# console-ifc.net
KiCad netlist of a schematic drawn in EAGLE
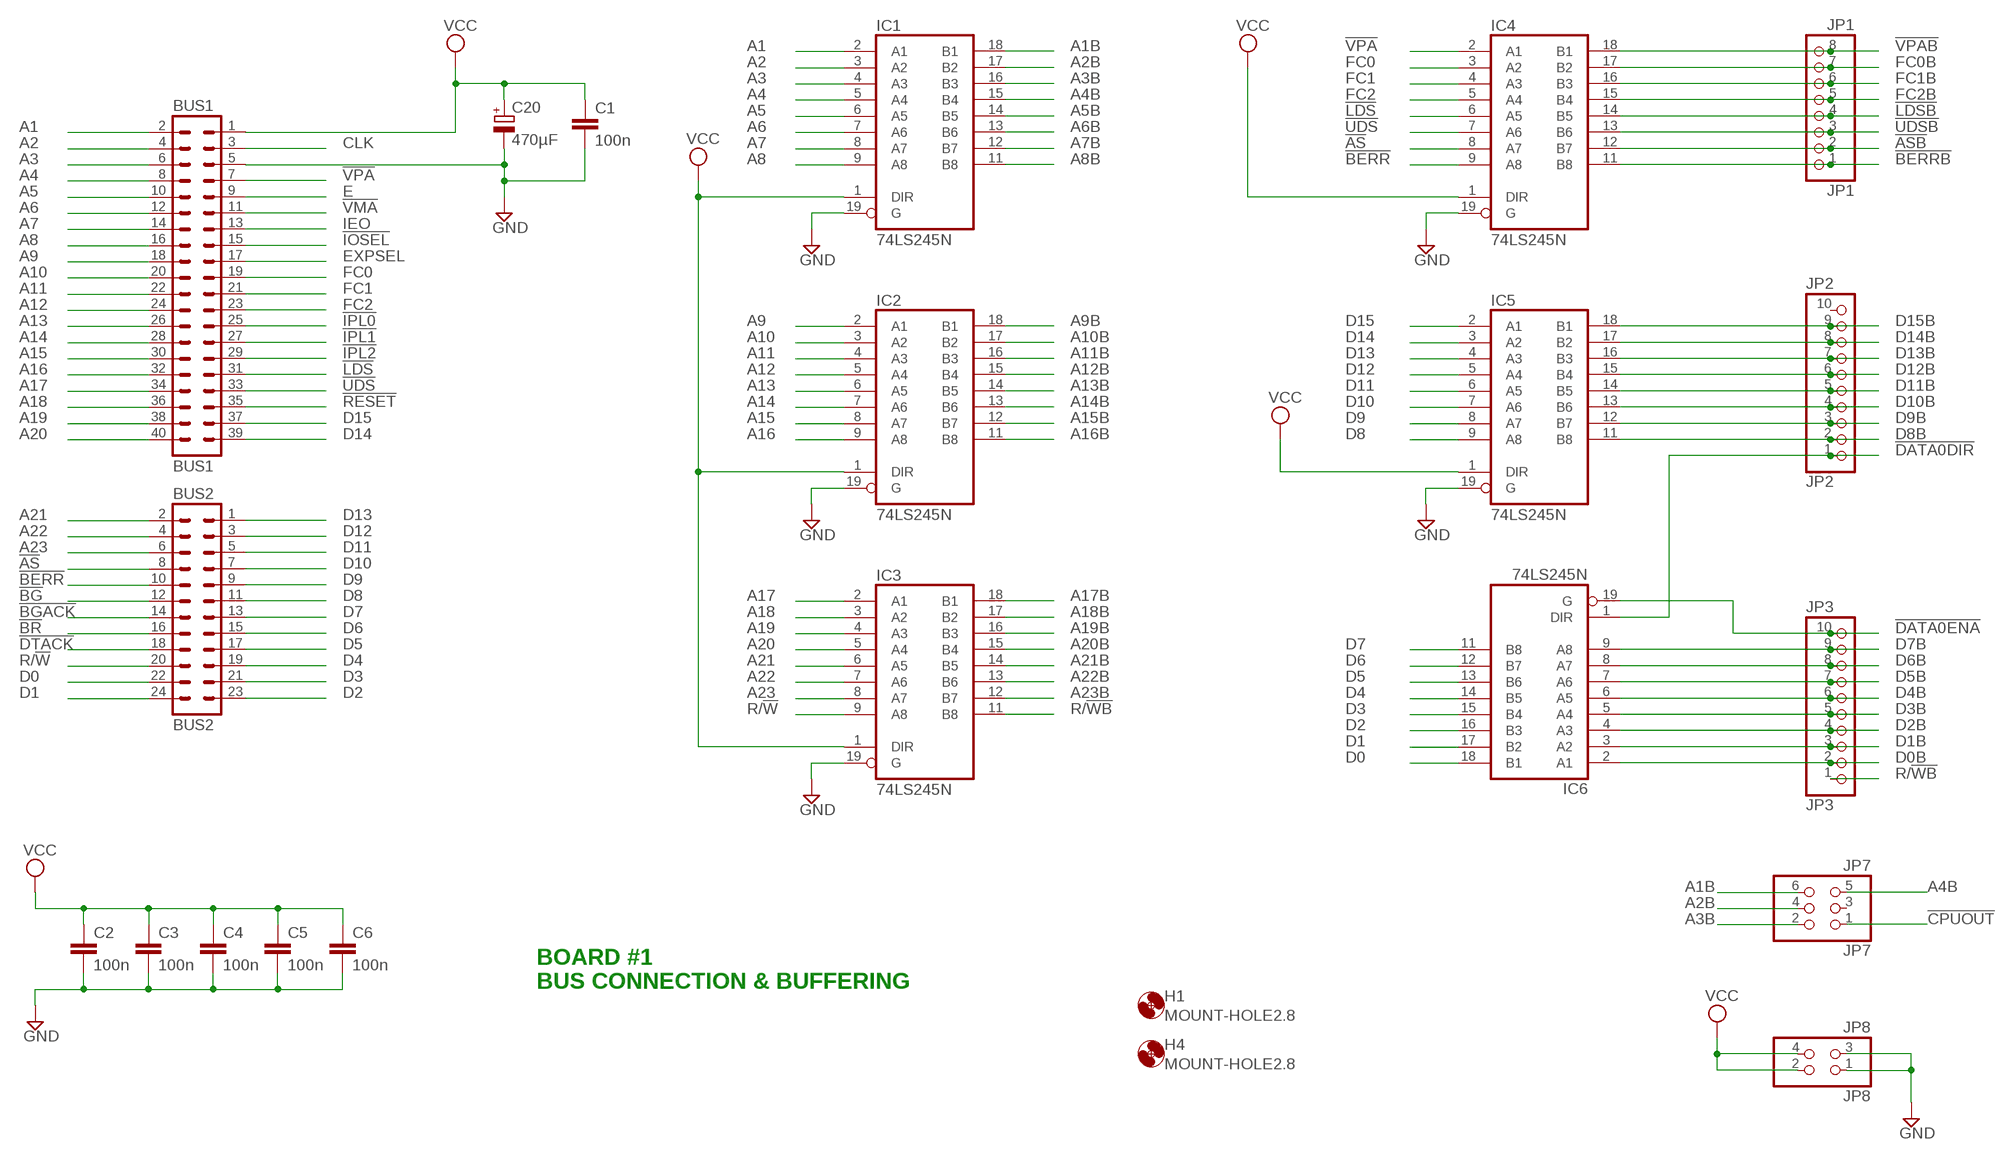
[diagram p0: schematic, sheet 1]
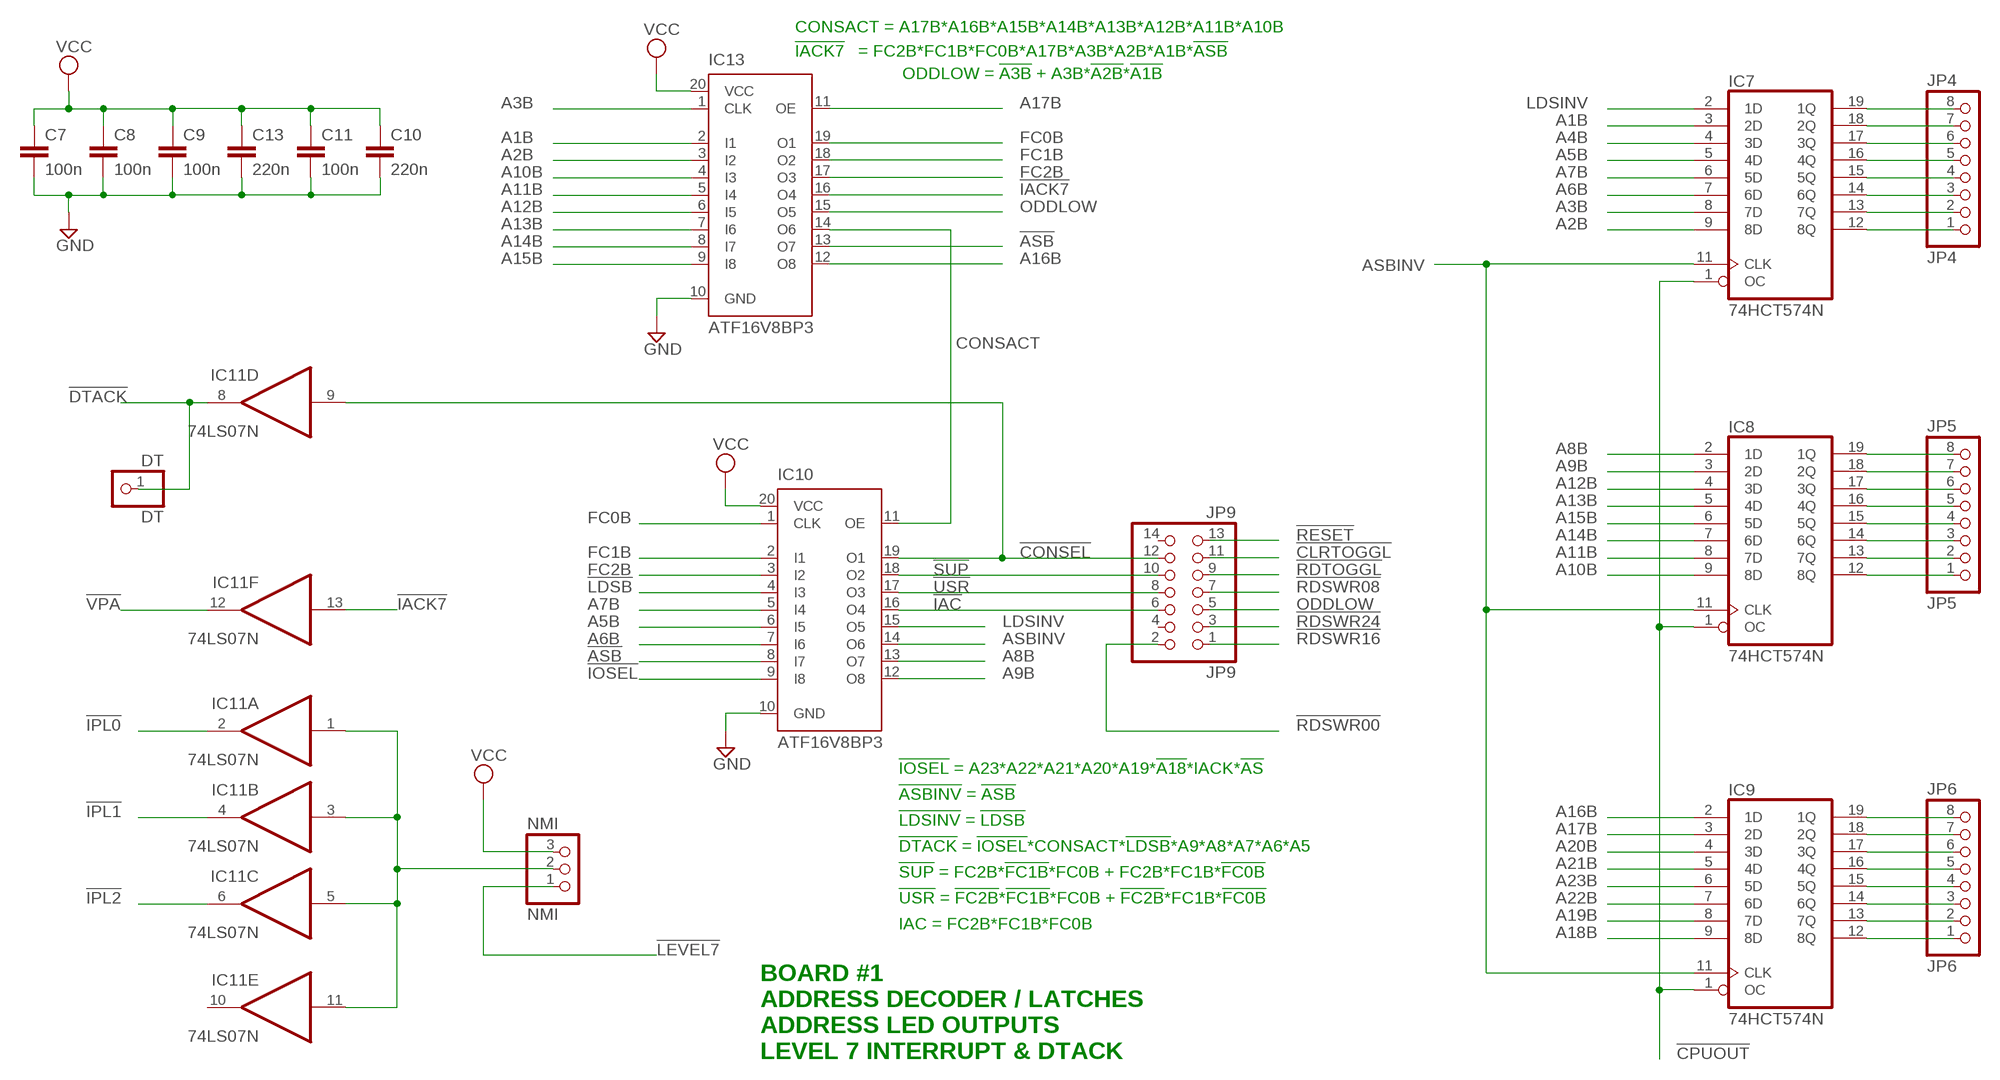
[diagram p1: schematic, sheet 2]
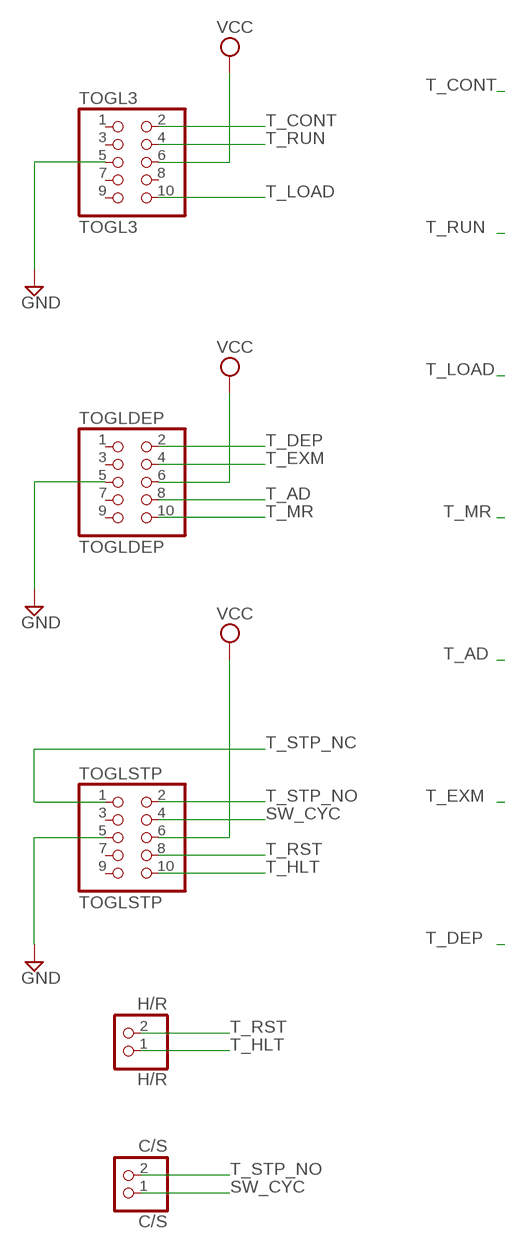
[diagram p2: schematic, sheet 3, part 1 of 2]
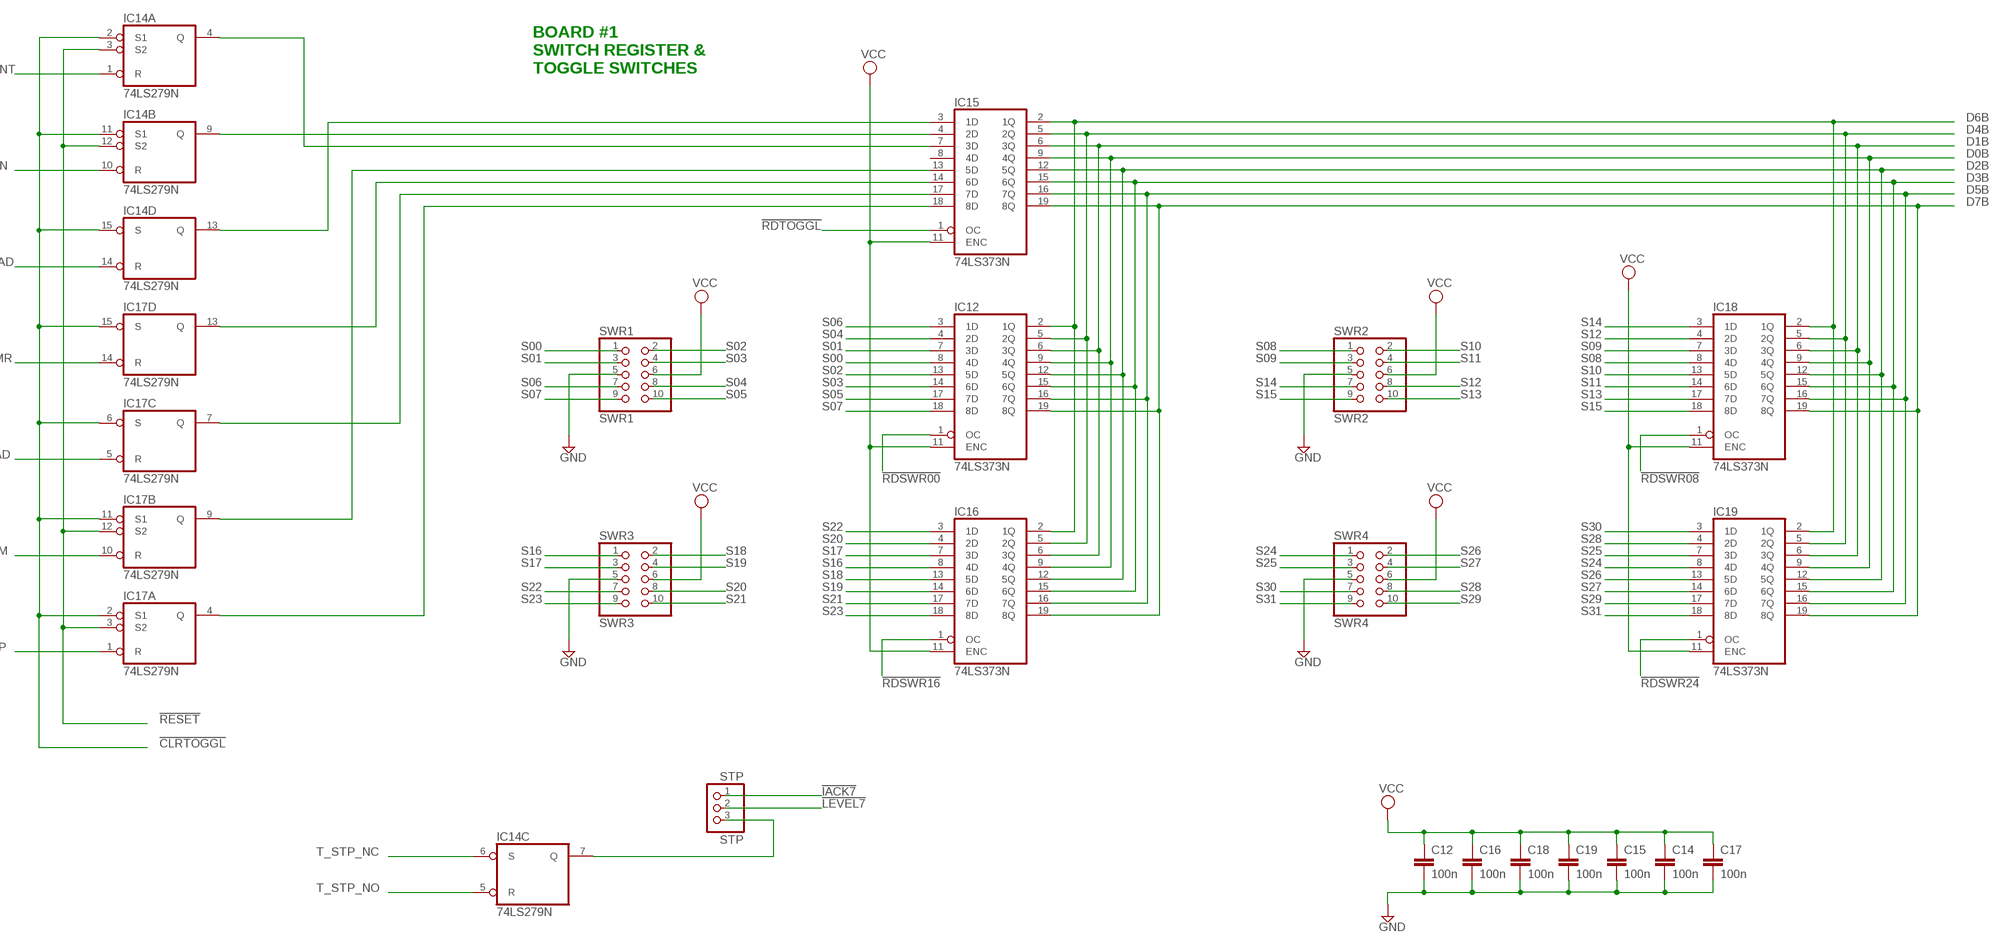
[diagram p3: schematic, sheet 3, part 2 of 2]

(export (version "E")
  (design (tool "Eeschema 10.0.6"))
  (components
    (comp (ref "C7")
      (value "100n")
      (footprint "eagle-import:C025-024X044")
      (libsource (lib "eagle-import") (part "C-EU025-024X044"))
    )
    (comp (ref "C8")
      (value "100n")
      (footprint "eagle-import:C025-024X044")
      (libsource (lib "eagle-import") (part "C-EU025-024X044"))
    )
    (comp (ref "C9")
      (value "100n")
      (footprint "eagle-import:C025-024X044")
      (libsource (lib "eagle-import") (part "C-EU025-024X044"))
    )
    (comp (ref "C10")
      (value "220n")
      (footprint "eagle-import:C025-024X044")
      (libsource (lib "eagle-import") (part "C-EU025-024X044"))
    )
    (comp (ref "C11")
      (value "100n")
      (footprint "eagle-import:C025-024X044")
      (libsource (lib "eagle-import") (part "C-EU025-024X044"))
    )
    (comp (ref "C13")
      (value "220n")
      (footprint "eagle-import:C025-024X044")
      (libsource (lib "eagle-import") (part "C-EU025-024X044"))
    )
    (comp (ref "DT")
      (value "DT")
      (footprint "eagle-import:1X01")
      (libsource (lib "eagle-import") (part "PINHD-1X1"))
    )
    (comp (ref "IC7")
      (value "74HCT574N")
      (footprint "eagle-import:DIL20")
      (libsource (lib "eagle-import") (part "74574NHCT"))
    )
    (comp (ref "IC8")
      (value "74HCT574N")
      (footprint "eagle-import:DIL20")
      (libsource (lib "eagle-import") (part "74574NHCT"))
    )
    (comp (ref "IC9")
      (value "74HCT574N")
      (footprint "eagle-import:DIL20")
      (libsource (lib "eagle-import") (part "74574NHCT"))
    )
    (comp (ref "IC10")
      (value "ATF16V8BP3")
      (footprint "eagle-import:DIL20")
      (fields (field (name "MPN") "ATF16V8CZ-15PU"))
      (libsource (lib "eagle-import") (part "ATF16V8BP3"))
    )
    (comp (ref "IC11")
      (value "74LS07N")
      (footprint "eagle-import:DIL14")
      (libsource (lib "eagle-import") (part "7407NLS"))
    )
    (comp (ref "IC13")
      (value "ATF16V8BP3")
      (footprint "eagle-import:DIL20")
      (fields (field (name "MPN") "ATF16V8CZ-15PU"))
      (libsource (lib "eagle-import") (part "ATF16V8BP3"))
    )
    (comp (ref "JP4")
      (value "JP4")
      (footprint "eagle-import:1X08")
      (libsource (lib "eagle-import") (part "PINHD-1X8"))
    )
    (comp (ref "JP5")
      (value "JP5")
      (footprint "eagle-import:1X08")
      (libsource (lib "eagle-import") (part "PINHD-1X8"))
    )
    (comp (ref "JP6")
      (value "JP6")
      (footprint "eagle-import:1X08")
      (libsource (lib "eagle-import") (part "PINHD-1X8"))
    )
    (comp (ref "JP9")
      (value "JP9")
      (footprint "eagle-import:2X07")
      (libsource (lib "eagle-import") (part "PINHD-2X7"))
    )
    (comp (ref "NMI")
      (value "NMI")
      (footprint "eagle-import:1X03")
      (libsource (lib "eagle-import") (part "PINHD-1X3"))
    )
    (comp (ref "C/S")
      (value "C/S")
      (footprint "eagle-import:1X02")
      (libsource (lib "eagle-import") (part "PINHD-1X2"))
    )
    (comp (ref "C12")
      (value "100n")
      (footprint "eagle-import:C025-024X044")
      (libsource (lib "eagle-import") (part "C-EU025-024X044"))
    )
    (comp (ref "C14")
      (value "100n")
      (footprint "eagle-import:C025-024X044")
      (libsource (lib "eagle-import") (part "C-EU025-024X044"))
    )
    (comp (ref "C15")
      (value "100n")
      (footprint "eagle-import:C025-024X044")
      (libsource (lib "eagle-import") (part "C-EU025-024X044"))
    )
    (comp (ref "C16")
      (value "100n")
      (footprint "eagle-import:C025-024X044")
      (libsource (lib "eagle-import") (part "C-EU025-024X044"))
    )
    (comp (ref "C17")
      (value "100n")
      (footprint "eagle-import:C025-024X044")
      (libsource (lib "eagle-import") (part "C-EU025-024X044"))
    )
    (comp (ref "C18")
      (value "100n")
      (footprint "eagle-import:C025-024X044")
      (libsource (lib "eagle-import") (part "C-EU025-024X044"))
    )
    (comp (ref "C19")
      (value "100n")
      (footprint "eagle-import:C025-024X044")
      (libsource (lib "eagle-import") (part "C-EU025-024X044"))
    )
    (comp (ref "H/R")
      (value "H/R")
      (footprint "eagle-import:1X02")
      (libsource (lib "eagle-import") (part "PINHD-1X2"))
    )
    (comp (ref "IC12")
      (value "74LS373N")
      (footprint "eagle-import:DIL20")
      (libsource (lib "eagle-import") (part "74373NLS"))
    )
    (comp (ref "IC14")
      (value "74LS279N")
      (footprint "eagle-import:DIL16")
      (libsource (lib "eagle-import") (part "74279NLS"))
    )
    (comp (ref "IC15")
      (value "74LS373N")
      (footprint "eagle-import:DIL20")
      (libsource (lib "eagle-import") (part "74373NLS"))
    )
    (comp (ref "IC16")
      (value "74LS373N")
      (footprint "eagle-import:DIL20")
      (libsource (lib "eagle-import") (part "74373NLS"))
    )
    (comp (ref "IC17")
      (value "74LS279N")
      (footprint "eagle-import:DIL16")
      (libsource (lib "eagle-import") (part "74279NLS"))
    )
    (comp (ref "IC18")
      (value "74LS373N")
      (footprint "eagle-import:DIL20")
      (libsource (lib "eagle-import") (part "74373NLS"))
    )
    (comp (ref "IC19")
      (value "74LS373N")
      (footprint "eagle-import:DIL20")
      (libsource (lib "eagle-import") (part "74373NLS"))
    )
    (comp (ref "STP")
      (value "STP")
      (footprint "eagle-import:1X03")
      (libsource (lib "eagle-import") (part "PINHD-1X3"))
    )
    (comp (ref "SWR1")
      (value "SWR1")
      (footprint "eagle-import:2X05")
      (libsource (lib "eagle-import") (part "PINHD-2X5"))
    )
    (comp (ref "SWR2")
      (value "SWR2")
      (footprint "eagle-import:2X05")
      (libsource (lib "eagle-import") (part "PINHD-2X5"))
    )
    (comp (ref "SWR3")
      (value "SWR3")
      (footprint "eagle-import:2X05")
      (libsource (lib "eagle-import") (part "PINHD-2X5"))
    )
    (comp (ref "SWR4")
      (value "SWR4")
      (footprint "eagle-import:2X05")
      (libsource (lib "eagle-import") (part "PINHD-2X5"))
    )
    (comp (ref "TOGL3")
      (value "TOGL3")
      (footprint "eagle-import:2X05")
      (libsource (lib "eagle-import") (part "PINHD-2X5"))
    )
    (comp (ref "TOGLDEP")
      (value "TOGLDEP")
      (footprint "eagle-import:2X05")
      (libsource (lib "eagle-import") (part "PINHD-2X5"))
    )
    (comp (ref "TOGLSTP")
      (value "TOGLSTP")
      (footprint "eagle-import:2X05")
      (libsource (lib "eagle-import") (part "PINHD-2X5"))
    )
    (comp (ref "BUS1")
      (value "BUS1")
      (footprint "eagle-import:MA20-2")
      (libsource (lib "eagle-import") (part "MA20-2"))
    )
    (comp (ref "BUS2")
      (value "BUS2")
      (footprint "eagle-import:MA12-2")
      (libsource (lib "eagle-import") (part "MA12-2"))
    )
    (comp (ref "C1")
      (value "100n")
      (footprint "eagle-import:C025-024X044")
      (libsource (lib "eagle-import") (part "C-EU025-024X044"))
    )
    (comp (ref "C2")
      (value "100n")
      (footprint "eagle-import:C025-024X044")
      (libsource (lib "eagle-import") (part "C-EU025-024X044"))
    )
    (comp (ref "C3")
      (value "100n")
      (footprint "eagle-import:C025-024X044")
      (libsource (lib "eagle-import") (part "C-EU025-024X044"))
    )
    (comp (ref "C4")
      (value "100n")
      (footprint "eagle-import:C025-024X044")
      (libsource (lib "eagle-import") (part "C-EU025-024X044"))
    )
    (comp (ref "C5")
      (value "100n")
      (footprint "eagle-import:C025-024X044")
      (libsource (lib "eagle-import") (part "C-EU025-024X044"))
    )
    (comp (ref "C6")
      (value "100n")
      (footprint "eagle-import:C025-024X044")
      (libsource (lib "eagle-import") (part "C-EU025-024X044"))
    )
    (comp (ref "C20")
      (value "470µF")
      (footprint "eagle-import:E2,5-7")
      (libsource (lib "eagle-import") (part "CPOL-EUE2.5-7"))
    )
    (comp (ref "H1")
      (value "MOUNT-HOLE2.8")
      (footprint "eagle-import:2,8")
      (libsource (lib "eagle-import") (part "MOUNT-HOLE2.8"))
    )
    (comp (ref "H4")
      (value "MOUNT-HOLE2.8")
      (footprint "eagle-import:2,8")
      (libsource (lib "eagle-import") (part "MOUNT-HOLE2.8"))
    )
    (comp (ref "IC1")
      (value "74LS245N")
      (footprint "eagle-import:DIL20")
      (libsource (lib "eagle-import") (part "74245NLS"))
    )
    (comp (ref "IC2")
      (value "74LS245N")
      (footprint "eagle-import:DIL20")
      (libsource (lib "eagle-import") (part "74245NLS"))
    )
    (comp (ref "IC3")
      (value "74LS245N")
      (footprint "eagle-import:DIL20")
      (libsource (lib "eagle-import") (part "74245NLS"))
    )
    (comp (ref "IC4")
      (value "74LS245N")
      (footprint "eagle-import:DIL20")
      (libsource (lib "eagle-import") (part "74245NLS"))
    )
    (comp (ref "IC5")
      (value "74LS245N")
      (footprint "eagle-import:DIL20")
      (libsource (lib "eagle-import") (part "74245NLS"))
    )
    (comp (ref "IC6")
      (value "74LS245N")
      (footprint "eagle-import:DIL20")
      (libsource (lib "eagle-import") (part "74245NLS"))
    )
    (comp (ref "JP1")
      (value "JP1")
      (footprint "eagle-import:1X08")
      (libsource (lib "eagle-import") (part "PINHD-1X8"))
    )
    (comp (ref "JP2")
      (value "JP2")
      (footprint "eagle-import:1X10")
      (libsource (lib "eagle-import") (part "PINHD-1X10"))
    )
    (comp (ref "JP3")
      (value "JP3")
      (footprint "eagle-import:1X10")
      (libsource (lib "eagle-import") (part "PINHD-1X10"))
    )
    (comp (ref "JP7")
      (value "JP7")
      (footprint "eagle-import:2X03")
      (libsource (lib "eagle-import") (part "PINHD-2X3"))
    )
    (comp (ref "JP8")
      (value "JP8")
      (footprint "eagle-import:2X02")
      (libsource (lib "eagle-import") (part "PINHD-2X2"))
    )
  )
  (nets
    (net (code "1") (name "A1") (class "Default")
      (node (ref "BUS1") (pin "2") (pinfunction "2_2") (pintype "passive"))
      (node (ref "IC1") (pin "2") (pinfunction "A1_2") (pintype "bidirectional"))
    )
    (net (code "2") (name "A1B") (class "Default")
      (node (ref "IC1") (pin "18") (pinfunction "B1_18") (pintype "bidirectional"))
      (node (ref "IC13") (pin "2") (pinfunction "I1_2") (pintype "input"))
      (node (ref "IC7") (pin "3") (pinfunction "2D_3") (pintype "input"))
      (node (ref "JP7") (pin "6") (pinfunction "6_6") (pintype "passive"))
    )
    (net (code "3") (name "A2") (class "Default")
      (node (ref "BUS1") (pin "4") (pinfunction "4_4") (pintype "passive"))
      (node (ref "IC1") (pin "3") (pinfunction "A2_3") (pintype "bidirectional"))
    )
    (net (code "4") (name "A2B") (class "Default")
      (node (ref "IC1") (pin "17") (pinfunction "B2_17") (pintype "bidirectional"))
      (node (ref "IC13") (pin "3") (pinfunction "I2_3") (pintype "input"))
      (node (ref "IC7") (pin "9") (pinfunction "8D_9") (pintype "input"))
      (node (ref "JP7") (pin "4") (pinfunction "4_4") (pintype "passive"))
    )
    (net (code "5") (name "A3") (class "Default")
      (node (ref "BUS1") (pin "6") (pinfunction "6_6") (pintype "passive"))
      (node (ref "IC1") (pin "4") (pinfunction "A3_4") (pintype "bidirectional"))
    )
    (net (code "6") (name "A3B") (class "Default")
      (node (ref "IC1") (pin "16") (pinfunction "B3_16") (pintype "bidirectional"))
      (node (ref "IC13") (pin "1") (pinfunction "CLK_1") (pintype "input"))
      (node (ref "IC7") (pin "8") (pinfunction "7D_8") (pintype "input"))
      (node (ref "JP7") (pin "2") (pinfunction "2_2") (pintype "passive"))
    )
    (net (code "7") (name "A4") (class "Default")
      (node (ref "BUS1") (pin "8") (pinfunction "8_8") (pintype "passive"))
      (node (ref "IC1") (pin "5") (pinfunction "A4_5") (pintype "bidirectional"))
    )
    (net (code "8") (name "A4B") (class "Default")
      (node (ref "IC1") (pin "15") (pinfunction "B4_15") (pintype "bidirectional"))
      (node (ref "IC7") (pin "4") (pinfunction "3D_4") (pintype "input"))
      (node (ref "JP7") (pin "5") (pinfunction "5_5") (pintype "passive"))
    )
    (net (code "9") (name "A5") (class "Default")
      (node (ref "BUS1") (pin "10") (pinfunction "10_10") (pintype "passive"))
      (node (ref "IC1") (pin "6") (pinfunction "A5_6") (pintype "bidirectional"))
    )
    (net (code "10") (name "A5B") (class "Default")
      (node (ref "IC1") (pin "14") (pinfunction "B5_14") (pintype "bidirectional"))
      (node (ref "IC10") (pin "6") (pinfunction "I5_6") (pintype "input"))
      (node (ref "IC7") (pin "5") (pinfunction "4D_5") (pintype "input"))
    )
    (net (code "11") (name "A6") (class "Default")
      (node (ref "BUS1") (pin "12") (pinfunction "12_12") (pintype "passive"))
      (node (ref "IC1") (pin "7") (pinfunction "A6_7") (pintype "bidirectional"))
    )
    (net (code "12") (name "A6B") (class "Default")
      (node (ref "IC1") (pin "13") (pinfunction "B6_13") (pintype "bidirectional"))
      (node (ref "IC10") (pin "7") (pinfunction "I6_7") (pintype "input"))
      (node (ref "IC7") (pin "7") (pinfunction "6D_7") (pintype "input"))
    )
    (net (code "13") (name "A7") (class "Default")
      (node (ref "BUS1") (pin "14") (pinfunction "14_14") (pintype "passive"))
      (node (ref "IC1") (pin "8") (pinfunction "A7_8") (pintype "bidirectional"))
    )
    (net (code "14") (name "A7B") (class "Default")
      (node (ref "IC1") (pin "12") (pinfunction "B7_12") (pintype "bidirectional"))
      (node (ref "IC10") (pin "5") (pinfunction "I4_5") (pintype "input"))
      (node (ref "IC7") (pin "6") (pinfunction "5D_6") (pintype "input"))
    )
    (net (code "15") (name "A8") (class "Default")
      (node (ref "BUS1") (pin "16") (pinfunction "16_16") (pintype "passive"))
      (node (ref "IC1") (pin "9") (pinfunction "A8_9") (pintype "bidirectional"))
    )
    (net (code "16") (name "A8B") (class "Default")
      (node (ref "IC1") (pin "11") (pinfunction "B8_11") (pintype "bidirectional"))
      (node (ref "IC10") (pin "13") (pinfunction "O7_13") (pintype "output"))
      (node (ref "IC8") (pin "2") (pinfunction "1D_2") (pintype "input"))
    )
    (net (code "17") (name "A9") (class "Default")
      (node (ref "BUS1") (pin "18") (pinfunction "18_18") (pintype "passive"))
      (node (ref "IC2") (pin "2") (pinfunction "A1_2") (pintype "bidirectional"))
    )
    (net (code "18") (name "A9B") (class "Default")
      (node (ref "IC10") (pin "12") (pinfunction "O8_12") (pintype "output"))
      (node (ref "IC2") (pin "18") (pinfunction "B1_18") (pintype "bidirectional"))
      (node (ref "IC8") (pin "3") (pinfunction "2D_3") (pintype "input"))
    )
    (net (code "19") (name "A10") (class "Default")
      (node (ref "BUS1") (pin "20") (pinfunction "20_20") (pintype "passive"))
      (node (ref "IC2") (pin "3") (pinfunction "A2_3") (pintype "bidirectional"))
    )
    (net (code "20") (name "A10B") (class "Default")
      (node (ref "IC13") (pin "4") (pinfunction "I3_4") (pintype "input"))
      (node (ref "IC2") (pin "17") (pinfunction "B2_17") (pintype "bidirectional"))
      (node (ref "IC8") (pin "9") (pinfunction "8D_9") (pintype "input"))
    )
    (net (code "21") (name "A11") (class "Default")
      (node (ref "BUS1") (pin "22") (pinfunction "22_22") (pintype "passive"))
      (node (ref "IC2") (pin "4") (pinfunction "A3_4") (pintype "bidirectional"))
    )
    (net (code "22") (name "A11B") (class "Default")
      (node (ref "IC13") (pin "5") (pinfunction "I4_5") (pintype "input"))
      (node (ref "IC2") (pin "16") (pinfunction "B3_16") (pintype "bidirectional"))
      (node (ref "IC8") (pin "8") (pinfunction "7D_8") (pintype "input"))
    )
    (net (code "23") (name "A12") (class "Default")
      (node (ref "BUS1") (pin "24") (pinfunction "24_24") (pintype "passive"))
      (node (ref "IC2") (pin "5") (pinfunction "A4_5") (pintype "bidirectional"))
    )
    (net (code "24") (name "A12B") (class "Default")
      (node (ref "IC13") (pin "6") (pinfunction "I5_6") (pintype "input"))
      (node (ref "IC2") (pin "15") (pinfunction "B4_15") (pintype "bidirectional"))
      (node (ref "IC8") (pin "4") (pinfunction "3D_4") (pintype "input"))
    )
    (net (code "25") (name "A13") (class "Default")
      (node (ref "BUS1") (pin "26") (pinfunction "26_26") (pintype "passive"))
      (node (ref "IC2") (pin "6") (pinfunction "A5_6") (pintype "bidirectional"))
    )
    (net (code "26") (name "A13B") (class "Default")
      (node (ref "IC13") (pin "7") (pinfunction "I6_7") (pintype "input"))
      (node (ref "IC2") (pin "14") (pinfunction "B5_14") (pintype "bidirectional"))
      (node (ref "IC8") (pin "5") (pinfunction "4D_5") (pintype "input"))
    )
    (net (code "27") (name "A14") (class "Default")
      (node (ref "BUS1") (pin "28") (pinfunction "28_28") (pintype "passive"))
      (node (ref "IC2") (pin "7") (pinfunction "A6_7") (pintype "bidirectional"))
    )
    (net (code "28") (name "A14B") (class "Default")
      (node (ref "IC13") (pin "8") (pinfunction "I7_8") (pintype "input"))
      (node (ref "IC2") (pin "13") (pinfunction "B6_13") (pintype "bidirectional"))
      (node (ref "IC8") (pin "7") (pinfunction "6D_7") (pintype "input"))
    )
    (net (code "29") (name "A15") (class "Default")
      (node (ref "BUS1") (pin "30") (pinfunction "30_30") (pintype "passive"))
      (node (ref "IC2") (pin "8") (pinfunction "A7_8") (pintype "bidirectional"))
    )
    (net (code "30") (name "A15B") (class "Default")
      (node (ref "IC13") (pin "9") (pinfunction "I8_9") (pintype "input"))
      (node (ref "IC2") (pin "12") (pinfunction "B7_12") (pintype "bidirectional"))
      (node (ref "IC8") (pin "6") (pinfunction "5D_6") (pintype "input"))
    )
    (net (code "31") (name "A16") (class "Default")
      (node (ref "BUS1") (pin "32") (pinfunction "32_32") (pintype "passive"))
      (node (ref "IC2") (pin "9") (pinfunction "A8_9") (pintype "bidirectional"))
    )
    (net (code "32") (name "A16B") (class "Default")
      (node (ref "IC13") (pin "12") (pinfunction "O8_12") (pintype "output"))
      (node (ref "IC2") (pin "11") (pinfunction "B8_11") (pintype "bidirectional"))
      (node (ref "IC9") (pin "2") (pinfunction "1D_2") (pintype "input"))
    )
    (net (code "33") (name "A17") (class "Default")
      (node (ref "BUS1") (pin "34") (pinfunction "34_34") (pintype "passive"))
      (node (ref "IC3") (pin "2") (pinfunction "A1_2") (pintype "bidirectional"))
    )
    (net (code "34") (name "A17B") (class "Default")
      (node (ref "IC13") (pin "11") (pinfunction "OE_11") (pintype "input"))
      (node (ref "IC3") (pin "18") (pinfunction "B1_18") (pintype "bidirectional"))
      (node (ref "IC9") (pin "3") (pinfunction "2D_3") (pintype "input"))
    )
    (net (code "35") (name "A18") (class "Default")
      (node (ref "BUS1") (pin "36") (pinfunction "36_36") (pintype "passive"))
      (node (ref "IC3") (pin "3") (pinfunction "A2_3") (pintype "bidirectional"))
    )
    (net (code "36") (name "A18B") (class "Default")
      (node (ref "IC3") (pin "17") (pinfunction "B2_17") (pintype "bidirectional"))
      (node (ref "IC9") (pin "9") (pinfunction "8D_9") (pintype "input"))
    )
    (net (code "37") (name "A19") (class "Default")
      (node (ref "BUS1") (pin "38") (pinfunction "38_38") (pintype "passive"))
      (node (ref "IC3") (pin "4") (pinfunction "A3_4") (pintype "bidirectional"))
    )
    (net (code "38") (name "A19B") (class "Default")
      (node (ref "IC3") (pin "16") (pinfunction "B3_16") (pintype "bidirectional"))
      (node (ref "IC9") (pin "8") (pinfunction "7D_8") (pintype "input"))
    )
    (net (code "39") (name "A20") (class "Default")
      (node (ref "BUS1") (pin "40") (pinfunction "40_40") (pintype "passive"))
      (node (ref "IC3") (pin "5") (pinfunction "A4_5") (pintype "bidirectional"))
    )
    (net (code "40") (name "A20B") (class "Default")
      (node (ref "IC3") (pin "15") (pinfunction "B4_15") (pintype "bidirectional"))
      (node (ref "IC9") (pin "4") (pinfunction "3D_4") (pintype "input"))
    )
    (net (code "41") (name "A21") (class "Default")
      (node (ref "BUS2") (pin "2") (pinfunction "2_2") (pintype "passive"))
      (node (ref "IC3") (pin "6") (pinfunction "A5_6") (pintype "bidirectional"))
    )
    (net (code "42") (name "A21B") (class "Default")
      (node (ref "IC3") (pin "14") (pinfunction "B5_14") (pintype "bidirectional"))
      (node (ref "IC9") (pin "5") (pinfunction "4D_5") (pintype "input"))
    )
    (net (code "43") (name "A22") (class "Default")
      (node (ref "BUS2") (pin "4") (pinfunction "4_4") (pintype "passive"))
      (node (ref "IC3") (pin "7") (pinfunction "A6_7") (pintype "bidirectional"))
    )
    (net (code "44") (name "A22B") (class "Default")
      (node (ref "IC3") (pin "13") (pinfunction "B6_13") (pintype "bidirectional"))
      (node (ref "IC9") (pin "7") (pinfunction "6D_7") (pintype "input"))
    )
    (net (code "45") (name "A23") (class "Default")
      (node (ref "BUS2") (pin "6") (pinfunction "6_6") (pintype "passive"))
      (node (ref "IC3") (pin "8") (pinfunction "A7_8") (pintype "bidirectional"))
    )
    (net (code "46") (name "A23B") (class "Default")
      (node (ref "IC3") (pin "12") (pinfunction "B7_12") (pintype "bidirectional"))
      (node (ref "IC9") (pin "6") (pinfunction "5D_6") (pintype "input"))
    )
    (net (code "47") (name "ASBINV") (class "Default")
      (node (ref "IC10") (pin "14") (pinfunction "O6_14") (pintype "output"))
      (node (ref "IC7") (pin "11") (pinfunction "CLK_11") (pintype "input"))
      (node (ref "IC8") (pin "11") (pinfunction "CLK_11") (pintype "input"))
      (node (ref "IC9") (pin "11") (pinfunction "CLK_11") (pintype "input"))
    )
    (net (code "48") (name "CLK") (class "Default")
      (node (ref "BUS1") (pin "3") (pinfunction "3_3") (pintype "passive"))
    )
    (net (code "49") (name "CONSACT") (class "Default")
      (node (ref "IC10") (pin "11") (pinfunction "OE_11") (pintype "input"))
      (node (ref "IC13") (pin "14") (pinfunction "O6_14") (pintype "output"))
    )
    (net (code "50") (name "D0") (class "Default")
      (node (ref "BUS2") (pin "22") (pinfunction "22_22") (pintype "passive"))
      (node (ref "IC6") (pin "18") (pinfunction "B1_18") (pintype "bidirectional"))
    )
    (net (code "51") (name "D0B") (class "Default")
      (node (ref "IC12") (pin "9") (pinfunction "4Q_9") (pintype "tri_state"))
      (node (ref "IC15") (pin "9") (pinfunction "4Q_9") (pintype "tri_state"))
      (node (ref "IC16") (pin "9") (pinfunction "4Q_9") (pintype "tri_state"))
      (node (ref "IC18") (pin "9") (pinfunction "4Q_9") (pintype "tri_state"))
      (node (ref "IC19") (pin "9") (pinfunction "4Q_9") (pintype "tri_state"))
      (node (ref "IC6") (pin "2") (pinfunction "A1_2") (pintype "bidirectional"))
      (node (ref "JP3") (pin "2") (pinfunction "2_2") (pintype "passive"))
    )
    (net (code "52") (name "D1") (class "Default")
      (node (ref "BUS2") (pin "24") (pinfunction "24_24") (pintype "passive"))
      (node (ref "IC6") (pin "17") (pinfunction "B2_17") (pintype "bidirectional"))
    )
    (net (code "53") (name "D1B") (class "Default")
      (node (ref "IC12") (pin "6") (pinfunction "3Q_6") (pintype "tri_state"))
      (node (ref "IC15") (pin "6") (pinfunction "3Q_6") (pintype "tri_state"))
      (node (ref "IC16") (pin "6") (pinfunction "3Q_6") (pintype "tri_state"))
      (node (ref "IC18") (pin "6") (pinfunction "3Q_6") (pintype "tri_state"))
      (node (ref "IC19") (pin "6") (pinfunction "3Q_6") (pintype "tri_state"))
      (node (ref "IC6") (pin "3") (pinfunction "A2_3") (pintype "bidirectional"))
      (node (ref "JP3") (pin "3") (pinfunction "3_3") (pintype "passive"))
    )
    (net (code "54") (name "D2") (class "Default")
      (node (ref "BUS2") (pin "23") (pinfunction "23_23") (pintype "passive"))
      (node (ref "IC6") (pin "16") (pinfunction "B3_16") (pintype "bidirectional"))
    )
    (net (code "55") (name "D2B") (class "Default")
      (node (ref "IC12") (pin "12") (pinfunction "5Q_12") (pintype "tri_state"))
      (node (ref "IC15") (pin "12") (pinfunction "5Q_12") (pintype "tri_state"))
      (node (ref "IC16") (pin "12") (pinfunction "5Q_12") (pintype "tri_state"))
      (node (ref "IC18") (pin "12") (pinfunction "5Q_12") (pintype "tri_state"))
      (node (ref "IC19") (pin "12") (pinfunction "5Q_12") (pintype "tri_state"))
      (node (ref "IC6") (pin "4") (pinfunction "A3_4") (pintype "bidirectional"))
      (node (ref "JP3") (pin "4") (pinfunction "4_4") (pintype "passive"))
    )
    (net (code "56") (name "D3") (class "Default")
      (node (ref "BUS2") (pin "21") (pinfunction "21_21") (pintype "passive"))
      (node (ref "IC6") (pin "15") (pinfunction "B4_15") (pintype "bidirectional"))
    )
    (net (code "57") (name "D3B") (class "Default")
      (node (ref "IC12") (pin "15") (pinfunction "6Q_15") (pintype "tri_state"))
      (node (ref "IC15") (pin "15") (pinfunction "6Q_15") (pintype "tri_state"))
      (node (ref "IC16") (pin "15") (pinfunction "6Q_15") (pintype "tri_state"))
      (node (ref "IC18") (pin "15") (pinfunction "6Q_15") (pintype "tri_state"))
      (node (ref "IC19") (pin "15") (pinfunction "6Q_15") (pintype "tri_state"))
      (node (ref "IC6") (pin "5") (pinfunction "A4_5") (pintype "bidirectional"))
      (node (ref "JP3") (pin "5") (pinfunction "5_5") (pintype "passive"))
    )
    (net (code "58") (name "D4") (class "Default")
      (node (ref "BUS2") (pin "19") (pinfunction "19_19") (pintype "passive"))
      (node (ref "IC6") (pin "14") (pinfunction "B5_14") (pintype "bidirectional"))
    )
    (net (code "59") (name "D4B") (class "Default")
      (node (ref "IC12") (pin "5") (pinfunction "2Q_5") (pintype "tri_state"))
      (node (ref "IC15") (pin "5") (pinfunction "2Q_5") (pintype "tri_state"))
      (node (ref "IC16") (pin "5") (pinfunction "2Q_5") (pintype "tri_state"))
      (node (ref "IC18") (pin "5") (pinfunction "2Q_5") (pintype "tri_state"))
      (node (ref "IC19") (pin "5") (pinfunction "2Q_5") (pintype "tri_state"))
      (node (ref "IC6") (pin "6") (pinfunction "A5_6") (pintype "bidirectional"))
      (node (ref "JP3") (pin "6") (pinfunction "6_6") (pintype "passive"))
    )
    (net (code "60") (name "D5") (class "Default")
      (node (ref "BUS2") (pin "17") (pinfunction "17_17") (pintype "passive"))
      (node (ref "IC6") (pin "13") (pinfunction "B6_13") (pintype "bidirectional"))
    )
    (net (code "61") (name "D5B") (class "Default")
      (node (ref "IC12") (pin "16") (pinfunction "7Q_16") (pintype "tri_state"))
      (node (ref "IC15") (pin "16") (pinfunction "7Q_16") (pintype "tri_state"))
      (node (ref "IC16") (pin "16") (pinfunction "7Q_16") (pintype "tri_state"))
      (node (ref "IC18") (pin "16") (pinfunction "7Q_16") (pintype "tri_state"))
      (node (ref "IC19") (pin "16") (pinfunction "7Q_16") (pintype "tri_state"))
      (node (ref "IC6") (pin "7") (pinfunction "A6_7") (pintype "bidirectional"))
      (node (ref "JP3") (pin "7") (pinfunction "7_7") (pintype "passive"))
    )
    (net (code "62") (name "D6") (class "Default")
      (node (ref "BUS2") (pin "15") (pinfunction "15_15") (pintype "passive"))
      (node (ref "IC6") (pin "12") (pinfunction "B7_12") (pintype "bidirectional"))
    )
    (net (code "63") (name "D6B") (class "Default")
      (node (ref "IC12") (pin "2") (pinfunction "1Q_2") (pintype "tri_state"))
      (node (ref "IC15") (pin "2") (pinfunction "1Q_2") (pintype "tri_state"))
      (node (ref "IC16") (pin "2") (pinfunction "1Q_2") (pintype "tri_state"))
      (node (ref "IC18") (pin "2") (pinfunction "1Q_2") (pintype "tri_state"))
      (node (ref "IC19") (pin "2") (pinfunction "1Q_2") (pintype "tri_state"))
      (node (ref "IC6") (pin "8") (pinfunction "A7_8") (pintype "bidirectional"))
      (node (ref "JP3") (pin "8") (pinfunction "8_8") (pintype "passive"))
    )
    (net (code "64") (name "D7") (class "Default")
      (node (ref "BUS2") (pin "13") (pinfunction "13_13") (pintype "passive"))
      (node (ref "IC6") (pin "11") (pinfunction "B8_11") (pintype "bidirectional"))
    )
    (net (code "65") (name "D7B") (class "Default")
      (node (ref "IC12") (pin "19") (pinfunction "8Q_19") (pintype "tri_state"))
      (node (ref "IC15") (pin "19") (pinfunction "8Q_19") (pintype "tri_state"))
      (node (ref "IC16") (pin "19") (pinfunction "8Q_19") (pintype "tri_state"))
      (node (ref "IC18") (pin "19") (pinfunction "8Q_19") (pintype "tri_state"))
      (node (ref "IC19") (pin "19") (pinfunction "8Q_19") (pintype "tri_state"))
      (node (ref "IC6") (pin "9") (pinfunction "A8_9") (pintype "bidirectional"))
      (node (ref "JP3") (pin "9") (pinfunction "9_9") (pintype "passive"))
    )
    (net (code "66") (name "D8") (class "Default")
      (node (ref "BUS2") (pin "11") (pinfunction "11_11") (pintype "passive"))
      (node (ref "IC5") (pin "9") (pinfunction "A8_9") (pintype "bidirectional"))
    )
    (net (code "67") (name "D8B") (class "Default")
      (node (ref "IC5") (pin "11") (pinfunction "B8_11") (pintype "bidirectional"))
      (node (ref "JP2") (pin "2") (pinfunction "2_2") (pintype "passive"))
    )
    (net (code "68") (name "D9") (class "Default")
      (node (ref "BUS2") (pin "9") (pinfunction "9_9") (pintype "passive"))
      (node (ref "IC5") (pin "8") (pinfunction "A7_8") (pintype "bidirectional"))
    )
    (net (code "69") (name "D9B") (class "Default")
      (node (ref "IC5") (pin "12") (pinfunction "B7_12") (pintype "bidirectional"))
      (node (ref "JP2") (pin "3") (pinfunction "3_3") (pintype "passive"))
    )
    (net (code "70") (name "D10") (class "Default")
      (node (ref "BUS2") (pin "7") (pinfunction "7_7") (pintype "passive"))
      (node (ref "IC5") (pin "7") (pinfunction "A6_7") (pintype "bidirectional"))
    )
    (net (code "71") (name "D10B") (class "Default")
      (node (ref "IC5") (pin "13") (pinfunction "B6_13") (pintype "bidirectional"))
      (node (ref "JP2") (pin "4") (pinfunction "4_4") (pintype "passive"))
    )
    (net (code "72") (name "D11") (class "Default")
      (node (ref "BUS2") (pin "5") (pinfunction "5_5") (pintype "passive"))
      (node (ref "IC5") (pin "6") (pinfunction "A5_6") (pintype "bidirectional"))
    )
    (net (code "73") (name "D11B") (class "Default")
      (node (ref "IC5") (pin "14") (pinfunction "B5_14") (pintype "bidirectional"))
      (node (ref "JP2") (pin "5") (pinfunction "5_5") (pintype "passive"))
    )
    (net (code "74") (name "D12") (class "Default")
      (node (ref "BUS2") (pin "3") (pinfunction "3_3") (pintype "passive"))
      (node (ref "IC5") (pin "5") (pinfunction "A4_5") (pintype "bidirectional"))
    )
    (net (code "75") (name "D12B") (class "Default")
      (node (ref "IC5") (pin "15") (pinfunction "B4_15") (pintype "bidirectional"))
      (node (ref "JP2") (pin "6") (pinfunction "6_6") (pintype "passive"))
    )
    (net (code "76") (name "D13") (class "Default")
      (node (ref "BUS2") (pin "1") (pinfunction "1_1") (pintype "passive"))
      (node (ref "IC5") (pin "4") (pinfunction "A3_4") (pintype "bidirectional"))
    )
    (net (code "77") (name "D13B") (class "Default")
      (node (ref "IC5") (pin "16") (pinfunction "B3_16") (pintype "bidirectional"))
      (node (ref "JP2") (pin "7") (pinfunction "7_7") (pintype "passive"))
    )
    (net (code "78") (name "D14") (class "Default")
      (node (ref "BUS1") (pin "39") (pinfunction "39_39") (pintype "passive"))
      (node (ref "IC5") (pin "3") (pinfunction "A2_3") (pintype "bidirectional"))
    )
    (net (code "79") (name "D14B") (class "Default")
      (node (ref "IC5") (pin "17") (pinfunction "B2_17") (pintype "bidirectional"))
      (node (ref "JP2") (pin "8") (pinfunction "8_8") (pintype "passive"))
    )
    (net (code "80") (name "D15") (class "Default")
      (node (ref "BUS1") (pin "37") (pinfunction "37_37") (pintype "passive"))
      (node (ref "IC5") (pin "2") (pinfunction "A1_2") (pintype "bidirectional"))
    )
    (net (code "81") (name "D15B") (class "Default")
      (node (ref "IC5") (pin "18") (pinfunction "B1_18") (pintype "bidirectional"))
      (node (ref "JP2") (pin "9") (pinfunction "9_9") (pintype "passive"))
    )
    (net (code "82") (name "E") (class "Default")
      (node (ref "BUS1") (pin "9") (pinfunction "9_9") (pintype "passive"))
    )
    (net (code "83") (name "EXPSEL") (class "Default")
      (node (ref "BUS1") (pin "17") (pinfunction "17_17") (pintype "passive"))
    )
    (net (code "84") (name "FC0") (class "Default")
      (node (ref "BUS1") (pin "19") (pinfunction "19_19") (pintype "passive"))
      (node (ref "IC4") (pin "3") (pinfunction "A2_3") (pintype "bidirectional"))
    )
    (net (code "85") (name "FC0B") (class "Default")
      (node (ref "IC10") (pin "1") (pinfunction "CLK_1") (pintype "input"))
      (node (ref "IC13") (pin "19") (pinfunction "O1_19") (pintype "output"))
      (node (ref "IC4") (pin "17") (pinfunction "B2_17") (pintype "bidirectional"))
      (node (ref "JP1") (pin "7") (pinfunction "7_7") (pintype "passive"))
    )
    (net (code "86") (name "FC1") (class "Default")
      (node (ref "BUS1") (pin "21") (pinfunction "21_21") (pintype "passive"))
      (node (ref "IC4") (pin "4") (pinfunction "A3_4") (pintype "bidirectional"))
    )
    (net (code "87") (name "FC1B") (class "Default")
      (node (ref "IC10") (pin "2") (pinfunction "I1_2") (pintype "input"))
      (node (ref "IC13") (pin "18") (pinfunction "O2_18") (pintype "output"))
      (node (ref "IC4") (pin "16") (pinfunction "B3_16") (pintype "bidirectional"))
      (node (ref "JP1") (pin "6") (pinfunction "6_6") (pintype "passive"))
    )
    (net (code "88") (name "FC2") (class "Default")
      (node (ref "BUS1") (pin "23") (pinfunction "23_23") (pintype "passive"))
      (node (ref "IC4") (pin "5") (pinfunction "A4_5") (pintype "bidirectional"))
    )
    (net (code "89") (name "FC2B") (class "Default")
      (node (ref "IC10") (pin "3") (pinfunction "I2_3") (pintype "input"))
      (node (ref "IC13") (pin "17") (pinfunction "O3_17") (pintype "output"))
      (node (ref "IC4") (pin "15") (pinfunction "B4_15") (pintype "bidirectional"))
      (node (ref "JP1") (pin "5") (pinfunction "5_5") (pintype "passive"))
    )
    (net (code "90") (name "GND") (class "Default")
      (node (ref "BUS1") (pin "5") (pinfunction "5_5") (pintype "passive"))
      (node (ref "C1") (pin "2") (pinfunction "2_2") (pintype "passive"))
      (node (ref "C10") (pin "2") (pinfunction "2_2") (pintype "passive"))
      (node (ref "C11") (pin "2") (pinfunction "2_2") (pintype "passive"))
      (node (ref "C12") (pin "2") (pinfunction "2_2") (pintype "passive"))
      (node (ref "C13") (pin "2") (pinfunction "2_2") (pintype "passive"))
      (node (ref "C14") (pin "2") (pinfunction "2_2") (pintype "passive"))
      (node (ref "C15") (pin "2") (pinfunction "2_2") (pintype "passive"))
      (node (ref "C16") (pin "2") (pinfunction "2_2") (pintype "passive"))
      (node (ref "C17") (pin "2") (pinfunction "2_2") (pintype "passive"))
      (node (ref "C18") (pin "2") (pinfunction "2_2") (pintype "passive"))
      (node (ref "C19") (pin "2") (pinfunction "2_2") (pintype "passive"))
      (node (ref "C2") (pin "2") (pinfunction "2_2") (pintype "passive"))
      (node (ref "C20") (pin "-") (pinfunction "-_-") (pintype "passive"))
      (node (ref "C3") (pin "2") (pinfunction "2_2") (pintype "passive"))
      (node (ref "C4") (pin "2") (pinfunction "2_2") (pintype "passive"))
      (node (ref "C5") (pin "2") (pinfunction "2_2") (pintype "passive"))
      (node (ref "C6") (pin "2") (pinfunction "2_2") (pintype "passive"))
      (node (ref "C7") (pin "2") (pinfunction "2_2") (pintype "passive"))
      (node (ref "C8") (pin "2") (pinfunction "2_2") (pintype "passive"))
      (node (ref "C9") (pin "2") (pinfunction "2_2") (pintype "passive"))
      (node (ref "IC1") (pin "19") (pinfunction "G_19") (pintype "input"))
      (node (ref "IC10") (pin "10") (pinfunction "GND_10") (pintype "power_in"))
      (node (ref "IC13") (pin "10") (pinfunction "GND_10") (pintype "power_in"))
      (node (ref "IC2") (pin "19") (pinfunction "G_19") (pintype "input"))
      (node (ref "IC3") (pin "19") (pinfunction "G_19") (pintype "input"))
      (node (ref "IC4") (pin "19") (pinfunction "G_19") (pintype "input"))
      (node (ref "IC5") (pin "19") (pinfunction "G_19") (pintype "input"))
      (node (ref "JP8") (pin "1") (pinfunction "1_1") (pintype "passive"))
      (node (ref "JP8") (pin "3") (pinfunction "3_3") (pintype "passive"))
      (node (ref "SWR1") (pin "5") (pinfunction "5_5") (pintype "passive"))
      (node (ref "SWR2") (pin "5") (pinfunction "5_5") (pintype "passive"))
      (node (ref "SWR3") (pin "5") (pinfunction "5_5") (pintype "passive"))
      (node (ref "SWR4") (pin "5") (pinfunction "5_5") (pintype "passive"))
      (node (ref "TOGL3") (pin "5") (pinfunction "5_5") (pintype "passive"))
      (node (ref "TOGLDEP") (pin "5") (pinfunction "5_5") (pintype "passive"))
      (node (ref "TOGLSTP") (pin "5") (pinfunction "5_5") (pintype "passive"))
    )
    (net (code "91") (name "IEO") (class "Default")
      (node (ref "BUS1") (pin "13") (pinfunction "13_13") (pintype "passive"))
    )
    (net (code "92") (name "LDSINV") (class "Default")
      (node (ref "IC10") (pin "15") (pinfunction "O5_15") (pintype "output"))
      (node (ref "IC7") (pin "2") (pinfunction "1D_2") (pintype "input"))
    )
    (net (code "93") (name "Net-(IC7A-1Q)") (class "Default")
      (node (ref "IC7") (pin "19") (pinfunction "1Q_19") (pintype "tri_state"))
      (node (ref "JP4") (pin "8") (pinfunction "8_8") (pintype "passive"))
    )
    (net (code "94") (name "Net-(IC7A-2Q)") (class "Default")
      (node (ref "IC7") (pin "18") (pinfunction "2Q_18") (pintype "tri_state"))
      (node (ref "JP4") (pin "7") (pinfunction "7_7") (pintype "passive"))
    )
    (net (code "95") (name "Net-(IC7A-3Q)") (class "Default")
      (node (ref "IC7") (pin "17") (pinfunction "3Q_17") (pintype "tri_state"))
      (node (ref "JP4") (pin "6") (pinfunction "6_6") (pintype "passive"))
    )
    (net (code "96") (name "Net-(IC7A-4Q)") (class "Default")
      (node (ref "IC7") (pin "16") (pinfunction "4Q_16") (pintype "tri_state"))
      (node (ref "JP4") (pin "5") (pinfunction "5_5") (pintype "passive"))
    )
    (net (code "97") (name "Net-(IC7A-5Q)") (class "Default")
      (node (ref "IC7") (pin "15") (pinfunction "5Q_15") (pintype "tri_state"))
      (node (ref "JP4") (pin "4") (pinfunction "4_4") (pintype "passive"))
    )
    (net (code "98") (name "Net-(IC7A-6Q)") (class "Default")
      (node (ref "IC7") (pin "14") (pinfunction "6Q_14") (pintype "tri_state"))
      (node (ref "JP4") (pin "3") (pinfunction "3_3") (pintype "passive"))
    )
    (net (code "99") (name "Net-(IC7A-7Q)") (class "Default")
      (node (ref "IC7") (pin "13") (pinfunction "7Q_13") (pintype "tri_state"))
      (node (ref "JP4") (pin "2") (pinfunction "2_2") (pintype "passive"))
    )
    (net (code "100") (name "Net-(IC7A-8Q)") (class "Default")
      (node (ref "IC7") (pin "12") (pinfunction "8Q_12") (pintype "tri_state"))
      (node (ref "JP4") (pin "1") (pinfunction "1_1") (pintype "passive"))
    )
    (net (code "101") (name "Net-(IC8A-1Q)") (class "Default")
      (node (ref "IC8") (pin "19") (pinfunction "1Q_19") (pintype "tri_state"))
      (node (ref "JP5") (pin "8") (pinfunction "8_8") (pintype "passive"))
    )
    (net (code "102") (name "Net-(IC8A-2Q)") (class "Default")
      (node (ref "IC8") (pin "18") (pinfunction "2Q_18") (pintype "tri_state"))
      (node (ref "JP5") (pin "7") (pinfunction "7_7") (pintype "passive"))
    )
    (net (code "103") (name "Net-(IC8A-3Q)") (class "Default")
      (node (ref "IC8") (pin "17") (pinfunction "3Q_17") (pintype "tri_state"))
      (node (ref "JP5") (pin "6") (pinfunction "6_6") (pintype "passive"))
    )
    (net (code "104") (name "Net-(IC8A-4Q)") (class "Default")
      (node (ref "IC8") (pin "16") (pinfunction "4Q_16") (pintype "tri_state"))
      (node (ref "JP5") (pin "5") (pinfunction "5_5") (pintype "passive"))
    )
    (net (code "105") (name "Net-(IC8A-5Q)") (class "Default")
      (node (ref "IC8") (pin "15") (pinfunction "5Q_15") (pintype "tri_state"))
      (node (ref "JP5") (pin "4") (pinfunction "4_4") (pintype "passive"))
    )
    (net (code "106") (name "Net-(IC8A-6Q)") (class "Default")
      (node (ref "IC8") (pin "14") (pinfunction "6Q_14") (pintype "tri_state"))
      (node (ref "JP5") (pin "3") (pinfunction "3_3") (pintype "passive"))
    )
    (net (code "107") (name "Net-(IC8A-7Q)") (class "Default")
      (node (ref "IC8") (pin "13") (pinfunction "7Q_13") (pintype "tri_state"))
      (node (ref "JP5") (pin "2") (pinfunction "2_2") (pintype "passive"))
    )
    (net (code "108") (name "Net-(IC8A-8Q)") (class "Default")
      (node (ref "IC8") (pin "12") (pinfunction "8Q_12") (pintype "tri_state"))
      (node (ref "JP5") (pin "1") (pinfunction "1_1") (pintype "passive"))
    )
    (net (code "109") (name "Net-(IC9A-1Q)") (class "Default")
      (node (ref "IC9") (pin "19") (pinfunction "1Q_19") (pintype "tri_state"))
      (node (ref "JP6") (pin "8") (pinfunction "8_8") (pintype "passive"))
    )
    (net (code "110") (name "Net-(IC9A-2Q)") (class "Default")
      (node (ref "IC9") (pin "18") (pinfunction "2Q_18") (pintype "tri_state"))
      (node (ref "JP6") (pin "7") (pinfunction "7_7") (pintype "passive"))
    )
    (net (code "111") (name "Net-(IC9A-3Q)") (class "Default")
      (node (ref "IC9") (pin "17") (pinfunction "3Q_17") (pintype "tri_state"))
      (node (ref "JP6") (pin "6") (pinfunction "6_6") (pintype "passive"))
    )
    (net (code "112") (name "Net-(IC9A-4Q)") (class "Default")
      (node (ref "IC9") (pin "16") (pinfunction "4Q_16") (pintype "tri_state"))
      (node (ref "JP6") (pin "5") (pinfunction "5_5") (pintype "passive"))
    )
    (net (code "113") (name "Net-(IC9A-5Q)") (class "Default")
      (node (ref "IC9") (pin "15") (pinfunction "5Q_15") (pintype "tri_state"))
      (node (ref "JP6") (pin "4") (pinfunction "4_4") (pintype "passive"))
    )
    (net (code "114") (name "Net-(IC9A-6Q)") (class "Default")
      (node (ref "IC9") (pin "14") (pinfunction "6Q_14") (pintype "tri_state"))
      (node (ref "JP6") (pin "3") (pinfunction "3_3") (pintype "passive"))
    )
    (net (code "115") (name "Net-(IC9A-7Q)") (class "Default")
      (node (ref "IC9") (pin "13") (pinfunction "7Q_13") (pintype "tri_state"))
      (node (ref "JP6") (pin "2") (pinfunction "2_2") (pintype "passive"))
    )
    (net (code "116") (name "Net-(IC9A-8Q)") (class "Default")
      (node (ref "IC9") (pin "12") (pinfunction "8Q_12") (pintype "tri_state"))
      (node (ref "JP6") (pin "1") (pinfunction "1_1") (pintype "passive"))
    )
    (net (code "117") (name "Net-(IC11A-I)") (class "Default")
      (node (ref "IC11") (pin "1") (pinfunction "I_1") (pintype "input"))
      (node (ref "IC11") (pin "11") (pinfunction "I_11") (pintype "input"))
      (node (ref "IC11") (pin "3") (pinfunction "I_3") (pintype "input"))
      (node (ref "IC11") (pin "5") (pinfunction "I_5") (pintype "input"))
      (node (ref "NMI") (pin "2") (pinfunction "2_2") (pintype "passive"))
    )
    (net (code "118") (name "Net-(IC14A-Q)") (class "Default")
      (node (ref "IC14") (pin "4") (pinfunction "Q_4") (pintype "output"))
      (node (ref "IC15") (pin "7") (pinfunction "3D_7") (pintype "input"))
    )
    (net (code "119") (name "Net-(IC14B-Q)") (class "Default")
      (node (ref "IC14") (pin "9") (pinfunction "Q_9") (pintype "output"))
      (node (ref "IC15") (pin "4") (pinfunction "2D_4") (pintype "input"))
    )
    (net (code "120") (name "Net-(IC14C-Q)") (class "Default")
      (node (ref "IC14") (pin "7") (pinfunction "Q_7") (pintype "output"))
      (node (ref "STP") (pin "3") (pinfunction "3_3") (pintype "passive"))
    )
    (net (code "121") (name "Net-(IC14D-Q)") (class "Default")
      (node (ref "IC14") (pin "13") (pinfunction "Q_13") (pintype "output"))
      (node (ref "IC15") (pin "3") (pinfunction "1D_3") (pintype "input"))
    )
    (net (code "122") (name "Net-(IC15A-5D)") (class "Default")
      (node (ref "IC15") (pin "13") (pinfunction "5D_13") (pintype "input"))
      (node (ref "IC17") (pin "9") (pinfunction "Q_9") (pintype "output"))
    )
    (net (code "123") (name "Net-(IC15A-6D)") (class "Default")
      (node (ref "IC15") (pin "14") (pinfunction "6D_14") (pintype "input"))
      (node (ref "IC17") (pin "13") (pinfunction "Q_13") (pintype "output"))
    )
    (net (code "124") (name "Net-(IC15A-7D)") (class "Default")
      (node (ref "IC15") (pin "17") (pinfunction "7D_17") (pintype "input"))
      (node (ref "IC17") (pin "7") (pinfunction "Q_7") (pintype "output"))
    )
    (net (code "125") (name "Net-(IC15A-8D)") (class "Default")
      (node (ref "IC15") (pin "18") (pinfunction "8D_18") (pintype "input"))
      (node (ref "IC17") (pin "4") (pinfunction "Q_4") (pintype "output"))
    )
    (net (code "126") (name "ODDLOW") (class "Default")
      (node (ref "IC13") (pin "15") (pinfunction "O5_15") (pintype "output"))
      (node (ref "JP9") (pin "5") (pinfunction "5_5") (pintype "passive"))
    )
    (net (code "127") (name "R{slash}~{WB}") (class "Default")
      (node (ref "IC3") (pin "11") (pinfunction "B8_11") (pintype "bidirectional"))
      (node (ref "JP3") (pin "1") (pinfunction "1_1") (pintype "passive"))
    )
    (net (code "128") (name "R{slash}~{W}") (class "Default")
      (node (ref "BUS2") (pin "20") (pinfunction "20_20") (pintype "passive"))
      (node (ref "IC3") (pin "9") (pinfunction "A8_9") (pintype "bidirectional"))
    )
    (net (code "129") (name "S00") (class "Default")
      (node (ref "IC12") (pin "8") (pinfunction "4D_8") (pintype "input"))
      (node (ref "SWR1") (pin "1") (pinfunction "1_1") (pintype "passive"))
    )
    (net (code "130") (name "S01") (class "Default")
      (node (ref "IC12") (pin "7") (pinfunction "3D_7") (pintype "input"))
      (node (ref "SWR1") (pin "3") (pinfunction "3_3") (pintype "passive"))
    )
    (net (code "131") (name "S02") (class "Default")
      (node (ref "IC12") (pin "13") (pinfunction "5D_13") (pintype "input"))
      (node (ref "SWR1") (pin "2") (pinfunction "2_2") (pintype "passive"))
    )
    (net (code "132") (name "S03") (class "Default")
      (node (ref "IC12") (pin "14") (pinfunction "6D_14") (pintype "input"))
      (node (ref "SWR1") (pin "4") (pinfunction "4_4") (pintype "passive"))
    )
    (net (code "133") (name "S04") (class "Default")
      (node (ref "IC12") (pin "4") (pinfunction "2D_4") (pintype "input"))
      (node (ref "SWR1") (pin "8") (pinfunction "8_8") (pintype "passive"))
    )
    (net (code "134") (name "S05") (class "Default")
      (node (ref "IC12") (pin "17") (pinfunction "7D_17") (pintype "input"))
      (node (ref "SWR1") (pin "10") (pinfunction "10_10") (pintype "passive"))
    )
    (net (code "135") (name "S06") (class "Default")
      (node (ref "IC12") (pin "3") (pinfunction "1D_3") (pintype "input"))
      (node (ref "SWR1") (pin "7") (pinfunction "7_7") (pintype "passive"))
    )
    (net (code "136") (name "S07") (class "Default")
      (node (ref "IC12") (pin "18") (pinfunction "8D_18") (pintype "input"))
      (node (ref "SWR1") (pin "9") (pinfunction "9_9") (pintype "passive"))
    )
    (net (code "137") (name "S08") (class "Default")
      (node (ref "IC18") (pin "8") (pinfunction "4D_8") (pintype "input"))
      (node (ref "SWR2") (pin "1") (pinfunction "1_1") (pintype "passive"))
    )
    (net (code "138") (name "S09") (class "Default")
      (node (ref "IC18") (pin "7") (pinfunction "3D_7") (pintype "input"))
      (node (ref "SWR2") (pin "3") (pinfunction "3_3") (pintype "passive"))
    )
    (net (code "139") (name "S10") (class "Default")
      (node (ref "IC18") (pin "13") (pinfunction "5D_13") (pintype "input"))
      (node (ref "SWR2") (pin "2") (pinfunction "2_2") (pintype "passive"))
    )
    (net (code "140") (name "S11") (class "Default")
      (node (ref "IC18") (pin "14") (pinfunction "6D_14") (pintype "input"))
      (node (ref "SWR2") (pin "4") (pinfunction "4_4") (pintype "passive"))
    )
    (net (code "141") (name "S12") (class "Default")
      (node (ref "IC18") (pin "4") (pinfunction "2D_4") (pintype "input"))
      (node (ref "SWR2") (pin "8") (pinfunction "8_8") (pintype "passive"))
    )
    (net (code "142") (name "S13") (class "Default")
      (node (ref "IC18") (pin "17") (pinfunction "7D_17") (pintype "input"))
      (node (ref "SWR2") (pin "10") (pinfunction "10_10") (pintype "passive"))
    )
    (net (code "143") (name "S14") (class "Default")
      (node (ref "IC18") (pin "3") (pinfunction "1D_3") (pintype "input"))
      (node (ref "SWR2") (pin "7") (pinfunction "7_7") (pintype "passive"))
    )
    (net (code "144") (name "S15") (class "Default")
      (node (ref "IC18") (pin "18") (pinfunction "8D_18") (pintype "input"))
      (node (ref "SWR2") (pin "9") (pinfunction "9_9") (pintype "passive"))
    )
    (net (code "145") (name "S16") (class "Default")
      (node (ref "IC16") (pin "8") (pinfunction "4D_8") (pintype "input"))
      (node (ref "SWR3") (pin "1") (pinfunction "1_1") (pintype "passive"))
    )
    (net (code "146") (name "S17") (class "Default")
      (node (ref "IC16") (pin "7") (pinfunction "3D_7") (pintype "input"))
      (node (ref "SWR3") (pin "3") (pinfunction "3_3") (pintype "passive"))
    )
    (net (code "147") (name "S18") (class "Default")
      (node (ref "IC16") (pin "13") (pinfunction "5D_13") (pintype "input"))
      (node (ref "SWR3") (pin "2") (pinfunction "2_2") (pintype "passive"))
    )
    (net (code "148") (name "S19") (class "Default")
      (node (ref "IC16") (pin "14") (pinfunction "6D_14") (pintype "input"))
      (node (ref "SWR3") (pin "4") (pinfunction "4_4") (pintype "passive"))
    )
    (net (code "149") (name "S20") (class "Default")
      (node (ref "IC16") (pin "4") (pinfunction "2D_4") (pintype "input"))
      (node (ref "SWR3") (pin "8") (pinfunction "8_8") (pintype "passive"))
    )
    (net (code "150") (name "S21") (class "Default")
      (node (ref "IC16") (pin "17") (pinfunction "7D_17") (pintype "input"))
      (node (ref "SWR3") (pin "10") (pinfunction "10_10") (pintype "passive"))
    )
    (net (code "151") (name "S22") (class "Default")
      (node (ref "IC16") (pin "3") (pinfunction "1D_3") (pintype "input"))
      (node (ref "SWR3") (pin "7") (pinfunction "7_7") (pintype "passive"))
    )
    (net (code "152") (name "S23") (class "Default")
      (node (ref "IC16") (pin "18") (pinfunction "8D_18") (pintype "input"))
      (node (ref "SWR3") (pin "9") (pinfunction "9_9") (pintype "passive"))
    )
    (net (code "153") (name "S24") (class "Default")
      (node (ref "IC19") (pin "8") (pinfunction "4D_8") (pintype "input"))
      (node (ref "SWR4") (pin "1") (pinfunction "1_1") (pintype "passive"))
    )
    (net (code "154") (name "S25") (class "Default")
      (node (ref "IC19") (pin "7") (pinfunction "3D_7") (pintype "input"))
      (node (ref "SWR4") (pin "3") (pinfunction "3_3") (pintype "passive"))
    )
    (net (code "155") (name "S26") (class "Default")
      (node (ref "IC19") (pin "13") (pinfunction "5D_13") (pintype "input"))
      (node (ref "SWR4") (pin "2") (pinfunction "2_2") (pintype "passive"))
    )
    (net (code "156") (name "S27") (class "Default")
      (node (ref "IC19") (pin "14") (pinfunction "6D_14") (pintype "input"))
      (node (ref "SWR4") (pin "4") (pinfunction "4_4") (pintype "passive"))
    )
    (net (code "157") (name "S28") (class "Default")
      (node (ref "IC19") (pin "4") (pinfunction "2D_4") (pintype "input"))
      (node (ref "SWR4") (pin "8") (pinfunction "8_8") (pintype "passive"))
    )
    (net (code "158") (name "S29") (class "Default")
      (node (ref "IC19") (pin "17") (pinfunction "7D_17") (pintype "input"))
      (node (ref "SWR4") (pin "10") (pinfunction "10_10") (pintype "passive"))
    )
    (net (code "159") (name "S30") (class "Default")
      (node (ref "IC19") (pin "3") (pinfunction "1D_3") (pintype "input"))
      (node (ref "SWR4") (pin "7") (pinfunction "7_7") (pintype "passive"))
    )
    (net (code "160") (name "S31") (class "Default")
      (node (ref "IC19") (pin "18") (pinfunction "8D_18") (pintype "input"))
      (node (ref "SWR4") (pin "9") (pinfunction "9_9") (pintype "passive"))
    )
    (net (code "161") (name "SW_CYC") (class "Default")
      (node (ref "C/S") (pin "1") (pinfunction "1_1") (pintype "passive"))
      (node (ref "TOGLSTP") (pin "4") (pinfunction "4_4") (pintype "passive"))
    )
    (net (code "162") (name "T_AD") (class "Default")
      (node (ref "IC17") (pin "5") (pinfunction "R_5") (pintype "input"))
      (node (ref "TOGLDEP") (pin "8") (pinfunction "8_8") (pintype "passive"))
    )
    (net (code "163") (name "T_CONT") (class "Default")
      (node (ref "IC14") (pin "1") (pinfunction "R_1") (pintype "input"))
      (node (ref "TOGL3") (pin "2") (pinfunction "2_2") (pintype "passive"))
    )
    (net (code "164") (name "T_DEP") (class "Default")
      (node (ref "IC17") (pin "1") (pinfunction "R_1") (pintype "input"))
      (node (ref "TOGLDEP") (pin "2") (pinfunction "2_2") (pintype "passive"))
    )
    (net (code "165") (name "T_EXM") (class "Default")
      (node (ref "IC17") (pin "10") (pinfunction "R_10") (pintype "input"))
      (node (ref "TOGLDEP") (pin "4") (pinfunction "4_4") (pintype "passive"))
    )
    (net (code "166") (name "T_HLT") (class "Default")
      (node (ref "H/R") (pin "1") (pinfunction "1_1") (pintype "passive"))
      (node (ref "TOGLSTP") (pin "10") (pinfunction "10_10") (pintype "passive"))
    )
    (net (code "167") (name "T_LOAD") (class "Default")
      (node (ref "IC14") (pin "14") (pinfunction "R_14") (pintype "input"))
      (node (ref "TOGL3") (pin "10") (pinfunction "10_10") (pintype "passive"))
    )
    (net (code "168") (name "T_MR") (class "Default")
      (node (ref "IC17") (pin "14") (pinfunction "R_14") (pintype "input"))
      (node (ref "TOGLDEP") (pin "10") (pinfunction "10_10") (pintype "passive"))
    )
    (net (code "169") (name "T_RST") (class "Default")
      (node (ref "H/R") (pin "2") (pinfunction "2_2") (pintype "passive"))
      (node (ref "TOGLSTP") (pin "8") (pinfunction "8_8") (pintype "passive"))
    )
    (net (code "170") (name "T_RUN") (class "Default")
      (node (ref "IC14") (pin "10") (pinfunction "R_10") (pintype "input"))
      (node (ref "TOGL3") (pin "4") (pinfunction "4_4") (pintype "passive"))
    )
    (net (code "171") (name "T_STP_NC") (class "Default")
      (node (ref "IC14") (pin "6") (pinfunction "S_6") (pintype "input"))
      (node (ref "TOGLSTP") (pin "1") (pinfunction "1_1") (pintype "passive"))
    )
    (net (code "172") (name "T_STP_NO") (class "Default")
      (node (ref "C/S") (pin "2") (pinfunction "2_2") (pintype "passive"))
      (node (ref "IC14") (pin "5") (pinfunction "R_5") (pintype "input"))
      (node (ref "TOGLSTP") (pin "2") (pinfunction "2_2") (pintype "passive"))
    )
    (net (code "173") (name "VCC") (class "Default")
      (node (ref "BUS1") (pin "1") (pinfunction "1_1") (pintype "passive"))
      (node (ref "C1") (pin "1") (pinfunction "1_1") (pintype "passive"))
      (node (ref "C10") (pin "1") (pinfunction "1_1") (pintype "passive"))
      (node (ref "C11") (pin "1") (pinfunction "1_1") (pintype "passive"))
      (node (ref "C12") (pin "1") (pinfunction "1_1") (pintype "passive"))
      (node (ref "C13") (pin "1") (pinfunction "1_1") (pintype "passive"))
      (node (ref "C14") (pin "1") (pinfunction "1_1") (pintype "passive"))
      (node (ref "C15") (pin "1") (pinfunction "1_1") (pintype "passive"))
      (node (ref "C16") (pin "1") (pinfunction "1_1") (pintype "passive"))
      (node (ref "C17") (pin "1") (pinfunction "1_1") (pintype "passive"))
      (node (ref "C18") (pin "1") (pinfunction "1_1") (pintype "passive"))
      (node (ref "C19") (pin "1") (pinfunction "1_1") (pintype "passive"))
      (node (ref "C2") (pin "1") (pinfunction "1_1") (pintype "passive"))
      (node (ref "C20") (pin "+") (pinfunction "+_+") (pintype "passive"))
      (node (ref "C3") (pin "1") (pinfunction "1_1") (pintype "passive"))
      (node (ref "C4") (pin "1") (pinfunction "1_1") (pintype "passive"))
      (node (ref "C5") (pin "1") (pinfunction "1_1") (pintype "passive"))
      (node (ref "C6") (pin "1") (pinfunction "1_1") (pintype "passive"))
      (node (ref "C7") (pin "1") (pinfunction "1_1") (pintype "passive"))
      (node (ref "C8") (pin "1") (pinfunction "1_1") (pintype "passive"))
      (node (ref "C9") (pin "1") (pinfunction "1_1") (pintype "passive"))
      (node (ref "IC1") (pin "1") (pinfunction "DIR_1") (pintype "input"))
      (node (ref "IC10") (pin "20") (pinfunction "VCC_20") (pintype "power_in"))
      (node (ref "IC12") (pin "11") (pinfunction "ENC_11") (pintype "input"))
      (node (ref "IC13") (pin "20") (pinfunction "VCC_20") (pintype "power_in"))
      (node (ref "IC15") (pin "11") (pinfunction "ENC_11") (pintype "input"))
      (node (ref "IC16") (pin "11") (pinfunction "ENC_11") (pintype "input"))
      (node (ref "IC18") (pin "11") (pinfunction "ENC_11") (pintype "input"))
      (node (ref "IC19") (pin "11") (pinfunction "ENC_11") (pintype "input"))
      (node (ref "IC2") (pin "1") (pinfunction "DIR_1") (pintype "input"))
      (node (ref "IC3") (pin "1") (pinfunction "DIR_1") (pintype "input"))
      (node (ref "IC4") (pin "1") (pinfunction "DIR_1") (pintype "input"))
      (node (ref "IC5") (pin "1") (pinfunction "DIR_1") (pintype "input"))
      (node (ref "JP8") (pin "2") (pinfunction "2_2") (pintype "passive"))
      (node (ref "JP8") (pin "4") (pinfunction "4_4") (pintype "passive"))
      (node (ref "NMI") (pin "3") (pinfunction "3_3") (pintype "passive"))
      (node (ref "SWR1") (pin "6") (pinfunction "6_6") (pintype "passive"))
      (node (ref "SWR2") (pin "6") (pinfunction "6_6") (pintype "passive"))
      (node (ref "SWR3") (pin "6") (pinfunction "6_6") (pintype "passive"))
      (node (ref "SWR4") (pin "6") (pinfunction "6_6") (pintype "passive"))
      (node (ref "TOGL3") (pin "6") (pinfunction "6_6") (pintype "passive"))
      (node (ref "TOGLDEP") (pin "6") (pinfunction "6_6") (pintype "passive"))
      (node (ref "TOGLSTP") (pin "6") (pinfunction "6_6") (pintype "passive"))
    )
    (net (code "174") (name "unconnected-(IC11E-O-Pad10)") (class "Default")
      (node (ref "IC11") (pin "10") (pinfunction "O_10") (pintype "open_collector"))
    )
    (net (code "175") (name "unconnected-(IC15A-4D-Pad8)") (class "Default")
      (node (ref "IC15") (pin "8") (pinfunction "4D_8") (pintype "input"))
    )
    (net (code "176") (name "unconnected-(JP2-Pad10)") (class "Default")
      (node (ref "JP2") (pin "10") (pinfunction "10_10") (pintype "passive"))
    )
    (net (code "177") (name "unconnected-(JP7-Pad3)") (class "Default")
      (node (ref "JP7") (pin "3") (pinfunction "3_3") (pintype "passive"))
    )
    (net (code "178") (name "unconnected-(JP9-Pad4)") (class "Default")
      (node (ref "JP9") (pin "4") (pinfunction "4_4") (pintype "passive"))
    )
    (net (code "179") (name "unconnected-(JP9-Pad14)") (class "Default")
      (node (ref "JP9") (pin "14") (pinfunction "14_14") (pintype "passive"))
    )
    (net (code "180") (name "unconnected-(TOGL3-Pad1)") (class "Default")
      (node (ref "TOGL3") (pin "1") (pinfunction "1_1") (pintype "passive"))
    )
    (net (code "181") (name "unconnected-(TOGL3-Pad3)") (class "Default")
      (node (ref "TOGL3") (pin "3") (pinfunction "3_3") (pintype "passive"))
    )
    (net (code "182") (name "unconnected-(TOGL3-Pad7)") (class "Default")
      (node (ref "TOGL3") (pin "7") (pinfunction "7_7") (pintype "passive"))
    )
    (net (code "183") (name "unconnected-(TOGL3-Pad8)") (class "Default")
      (node (ref "TOGL3") (pin "8") (pinfunction "8_8") (pintype "passive"))
    )
    (net (code "184") (name "unconnected-(TOGL3-Pad9)") (class "Default")
      (node (ref "TOGL3") (pin "9") (pinfunction "9_9") (pintype "passive"))
    )
    (net (code "185") (name "unconnected-(TOGLDEP-Pad1)") (class "Default")
      (node (ref "TOGLDEP") (pin "1") (pinfunction "1_1") (pintype "passive"))
    )
    (net (code "186") (name "unconnected-(TOGLDEP-Pad3)") (class "Default")
      (node (ref "TOGLDEP") (pin "3") (pinfunction "3_3") (pintype "passive"))
    )
    (net (code "187") (name "unconnected-(TOGLDEP-Pad7)") (class "Default")
      (node (ref "TOGLDEP") (pin "7") (pinfunction "7_7") (pintype "passive"))
    )
    (net (code "188") (name "unconnected-(TOGLDEP-Pad9)") (class "Default")
      (node (ref "TOGLDEP") (pin "9") (pinfunction "9_9") (pintype "passive"))
    )
    (net (code "189") (name "unconnected-(TOGLSTP-Pad3)") (class "Default")
      (node (ref "TOGLSTP") (pin "3") (pinfunction "3_3") (pintype "passive"))
    )
    (net (code "190") (name "unconnected-(TOGLSTP-Pad7)") (class "Default")
      (node (ref "TOGLSTP") (pin "7") (pinfunction "7_7") (pintype "passive"))
    )
    (net (code "191") (name "unconnected-(TOGLSTP-Pad9)") (class "Default")
      (node (ref "TOGLSTP") (pin "9") (pinfunction "9_9") (pintype "passive"))
    )
    (net (code "192") (name "~{ASB}") (class "Default")
      (node (ref "IC10") (pin "8") (pinfunction "I7_8") (pintype "input"))
      (node (ref "IC13") (pin "13") (pinfunction "O7_13") (pintype "output"))
      (node (ref "IC4") (pin "12") (pinfunction "B7_12") (pintype "bidirectional"))
      (node (ref "JP1") (pin "2") (pinfunction "2_2") (pintype "passive"))
    )
    (net (code "193") (name "~{AS}") (class "Default")
      (node (ref "BUS2") (pin "8") (pinfunction "8_8") (pintype "passive"))
      (node (ref "IC4") (pin "8") (pinfunction "A7_8") (pintype "bidirectional"))
    )
    (net (code "194") (name "~{BERRB}") (class "Default")
      (node (ref "IC4") (pin "11") (pinfunction "B8_11") (pintype "bidirectional"))
      (node (ref "JP1") (pin "1") (pinfunction "1_1") (pintype "passive"))
    )
    (net (code "195") (name "~{BERR}") (class "Default")
      (node (ref "BUS2") (pin "10") (pinfunction "10_10") (pintype "passive"))
      (node (ref "IC4") (pin "9") (pinfunction "A8_9") (pintype "bidirectional"))
    )
    (net (code "196") (name "~{BGACK}") (class "Default")
      (node (ref "BUS2") (pin "14") (pinfunction "14_14") (pintype "passive"))
    )
    (net (code "197") (name "~{BG}") (class "Default")
      (node (ref "BUS2") (pin "12") (pinfunction "12_12") (pintype "passive"))
    )
    (net (code "198") (name "~{BR}") (class "Default")
      (node (ref "BUS2") (pin "16") (pinfunction "16_16") (pintype "passive"))
    )
    (net (code "199") (name "~{CLRTOGGL}") (class "Default")
      (node (ref "IC14") (pin "11") (pinfunction "S1_11") (pintype "input"))
      (node (ref "IC14") (pin "15") (pinfunction "S_15") (pintype "input"))
      (node (ref "IC14") (pin "2") (pinfunction "S1_2") (pintype "input"))
      (node (ref "IC17") (pin "11") (pinfunction "S1_11") (pintype "input"))
      (node (ref "IC17") (pin "15") (pinfunction "S_15") (pintype "input"))
      (node (ref "IC17") (pin "2") (pinfunction "S1_2") (pintype "input"))
      (node (ref "IC17") (pin "6") (pinfunction "S_6") (pintype "input"))
      (node (ref "JP9") (pin "11") (pinfunction "11_11") (pintype "passive"))
    )
    (net (code "200") (name "~{CONSEL}") (class "Default")
      (node (ref "IC10") (pin "19") (pinfunction "O1_19") (pintype "output"))
      (node (ref "IC11") (pin "9") (pinfunction "I_9") (pintype "input"))
      (node (ref "JP9") (pin "12") (pinfunction "12_12") (pintype "passive"))
    )
    (net (code "201") (name "~{CPUOUT}") (class "Default")
      (node (ref "IC7") (pin "1") (pinfunction "OC_1") (pintype "input"))
      (node (ref "IC8") (pin "1") (pinfunction "OC_1") (pintype "input"))
      (node (ref "IC9") (pin "1") (pinfunction "OC_1") (pintype "input"))
      (node (ref "JP7") (pin "1") (pinfunction "1_1") (pintype "passive"))
    )
    (net (code "202") (name "~{DATA0DIR}") (class "Default")
      (node (ref "IC6") (pin "1") (pinfunction "DIR_1") (pintype "input"))
      (node (ref "JP2") (pin "1") (pinfunction "1_1") (pintype "passive"))
    )
    (net (code "203") (name "~{DATA0ENA}") (class "Default")
      (node (ref "IC6") (pin "19") (pinfunction "G_19") (pintype "input"))
      (node (ref "JP3") (pin "10") (pinfunction "10_10") (pintype "passive"))
    )
    (net (code "204") (name "~{DTACK}") (class "Default")
      (node (ref "BUS2") (pin "18") (pinfunction "18_18") (pintype "passive"))
      (node (ref "DT") (pin "1") (pinfunction "1_1") (pintype "passive"))
      (node (ref "IC11") (pin "8") (pinfunction "O_8") (pintype "open_collector"))
    )
    (net (code "205") (name "~{IACK7}") (class "Default")
      (node (ref "IC11") (pin "13") (pinfunction "I_13") (pintype "input"))
      (node (ref "IC13") (pin "16") (pinfunction "O4_16") (pintype "output"))
      (node (ref "STP") (pin "1") (pinfunction "1_1") (pintype "passive"))
    )
    (net (code "206") (name "~{IAC}") (class "Default")
      (node (ref "IC10") (pin "16") (pinfunction "O4_16") (pintype "output"))
      (node (ref "JP9") (pin "6") (pinfunction "6_6") (pintype "passive"))
    )
    (net (code "207") (name "~{IOSEL}") (class "Default")
      (node (ref "BUS1") (pin "15") (pinfunction "15_15") (pintype "passive"))
      (node (ref "IC10") (pin "9") (pinfunction "I8_9") (pintype "input"))
    )
    (net (code "208") (name "~{IPL0}") (class "Default")
      (node (ref "BUS1") (pin "25") (pinfunction "25_25") (pintype "passive"))
      (node (ref "IC11") (pin "2") (pinfunction "O_2") (pintype "open_collector"))
    )
    (net (code "209") (name "~{IPL1}") (class "Default")
      (node (ref "BUS1") (pin "27") (pinfunction "27_27") (pintype "passive"))
      (node (ref "IC11") (pin "4") (pinfunction "O_4") (pintype "open_collector"))
    )
    (net (code "210") (name "~{IPL2}") (class "Default")
      (node (ref "BUS1") (pin "29") (pinfunction "29_29") (pintype "passive"))
      (node (ref "IC11") (pin "6") (pinfunction "O_6") (pintype "open_collector"))
    )
    (net (code "211") (name "~{LDSB}") (class "Default")
      (node (ref "IC10") (pin "4") (pinfunction "I3_4") (pintype "input"))
      (node (ref "IC4") (pin "14") (pinfunction "B5_14") (pintype "bidirectional"))
      (node (ref "JP1") (pin "4") (pinfunction "4_4") (pintype "passive"))
    )
    (net (code "212") (name "~{LDS}") (class "Default")
      (node (ref "BUS1") (pin "31") (pinfunction "31_31") (pintype "passive"))
      (node (ref "IC4") (pin "6") (pinfunction "A5_6") (pintype "bidirectional"))
    )
    (net (code "213") (name "~{LEVEL7}") (class "Default")
      (node (ref "NMI") (pin "1") (pinfunction "1_1") (pintype "passive"))
      (node (ref "STP") (pin "2") (pinfunction "2_2") (pintype "passive"))
    )
    (net (code "214") (name "~{RDSWR00}") (class "Default")
      (node (ref "IC12") (pin "1") (pinfunction "OC_1") (pintype "input"))
      (node (ref "JP9") (pin "2") (pinfunction "2_2") (pintype "passive"))
    )
    (net (code "215") (name "~{RDSWR08}") (class "Default")
      (node (ref "IC18") (pin "1") (pinfunction "OC_1") (pintype "input"))
      (node (ref "JP9") (pin "7") (pinfunction "7_7") (pintype "passive"))
    )
    (net (code "216") (name "~{RDSWR16}") (class "Default")
      (node (ref "IC16") (pin "1") (pinfunction "OC_1") (pintype "input"))
      (node (ref "JP9") (pin "1") (pinfunction "1_1") (pintype "passive"))
    )
    (net (code "217") (name "~{RDSWR24}") (class "Default")
      (node (ref "IC19") (pin "1") (pinfunction "OC_1") (pintype "input"))
      (node (ref "JP9") (pin "3") (pinfunction "3_3") (pintype "passive"))
    )
    (net (code "218") (name "~{RDTOGGL}") (class "Default")
      (node (ref "IC15") (pin "1") (pinfunction "OC_1") (pintype "input"))
      (node (ref "JP9") (pin "9") (pinfunction "9_9") (pintype "passive"))
    )
    (net (code "219") (name "~{RESET}") (class "Default")
      (node (ref "BUS1") (pin "35") (pinfunction "35_35") (pintype "passive"))
      (node (ref "IC14") (pin "12") (pinfunction "S2_12") (pintype "input"))
      (node (ref "IC14") (pin "3") (pinfunction "S2_3") (pintype "input"))
      (node (ref "IC17") (pin "12") (pinfunction "S2_12") (pintype "input"))
      (node (ref "IC17") (pin "3") (pinfunction "S2_3") (pintype "input"))
      (node (ref "JP9") (pin "13") (pinfunction "13_13") (pintype "passive"))
    )
    (net (code "220") (name "~{SUP}") (class "Default")
      (node (ref "IC10") (pin "18") (pinfunction "O2_18") (pintype "output"))
      (node (ref "JP9") (pin "10") (pinfunction "10_10") (pintype "passive"))
    )
    (net (code "221") (name "~{UDSB}") (class "Default")
      (node (ref "IC4") (pin "13") (pinfunction "B6_13") (pintype "bidirectional"))
      (node (ref "JP1") (pin "3") (pinfunction "3_3") (pintype "passive"))
    )
    (net (code "222") (name "~{UDS}") (class "Default")
      (node (ref "BUS1") (pin "33") (pinfunction "33_33") (pintype "passive"))
      (node (ref "IC4") (pin "7") (pinfunction "A6_7") (pintype "bidirectional"))
    )
    (net (code "223") (name "~{USR}") (class "Default")
      (node (ref "IC10") (pin "17") (pinfunction "O3_17") (pintype "output"))
      (node (ref "JP9") (pin "8") (pinfunction "8_8") (pintype "passive"))
    )
    (net (code "224") (name "~{VMA}") (class "Default")
      (node (ref "BUS1") (pin "11") (pinfunction "11_11") (pintype "passive"))
    )
    (net (code "225") (name "~{VPAB}") (class "Default")
      (node (ref "IC4") (pin "18") (pinfunction "B1_18") (pintype "bidirectional"))
      (node (ref "JP1") (pin "8") (pinfunction "8_8") (pintype "passive"))
    )
    (net (code "226") (name "~{VPA}") (class "Default")
      (node (ref "BUS1") (pin "7") (pinfunction "7_7") (pintype "passive"))
      (node (ref "IC11") (pin "12") (pinfunction "O_12") (pintype "open_collector"))
      (node (ref "IC4") (pin "2") (pinfunction "A1_2") (pintype "bidirectional"))
    )
  )
)
